# Sensor_Acquisition_Board_Rev5.net
KiCad netlist of a schematic drawn in EAGLE
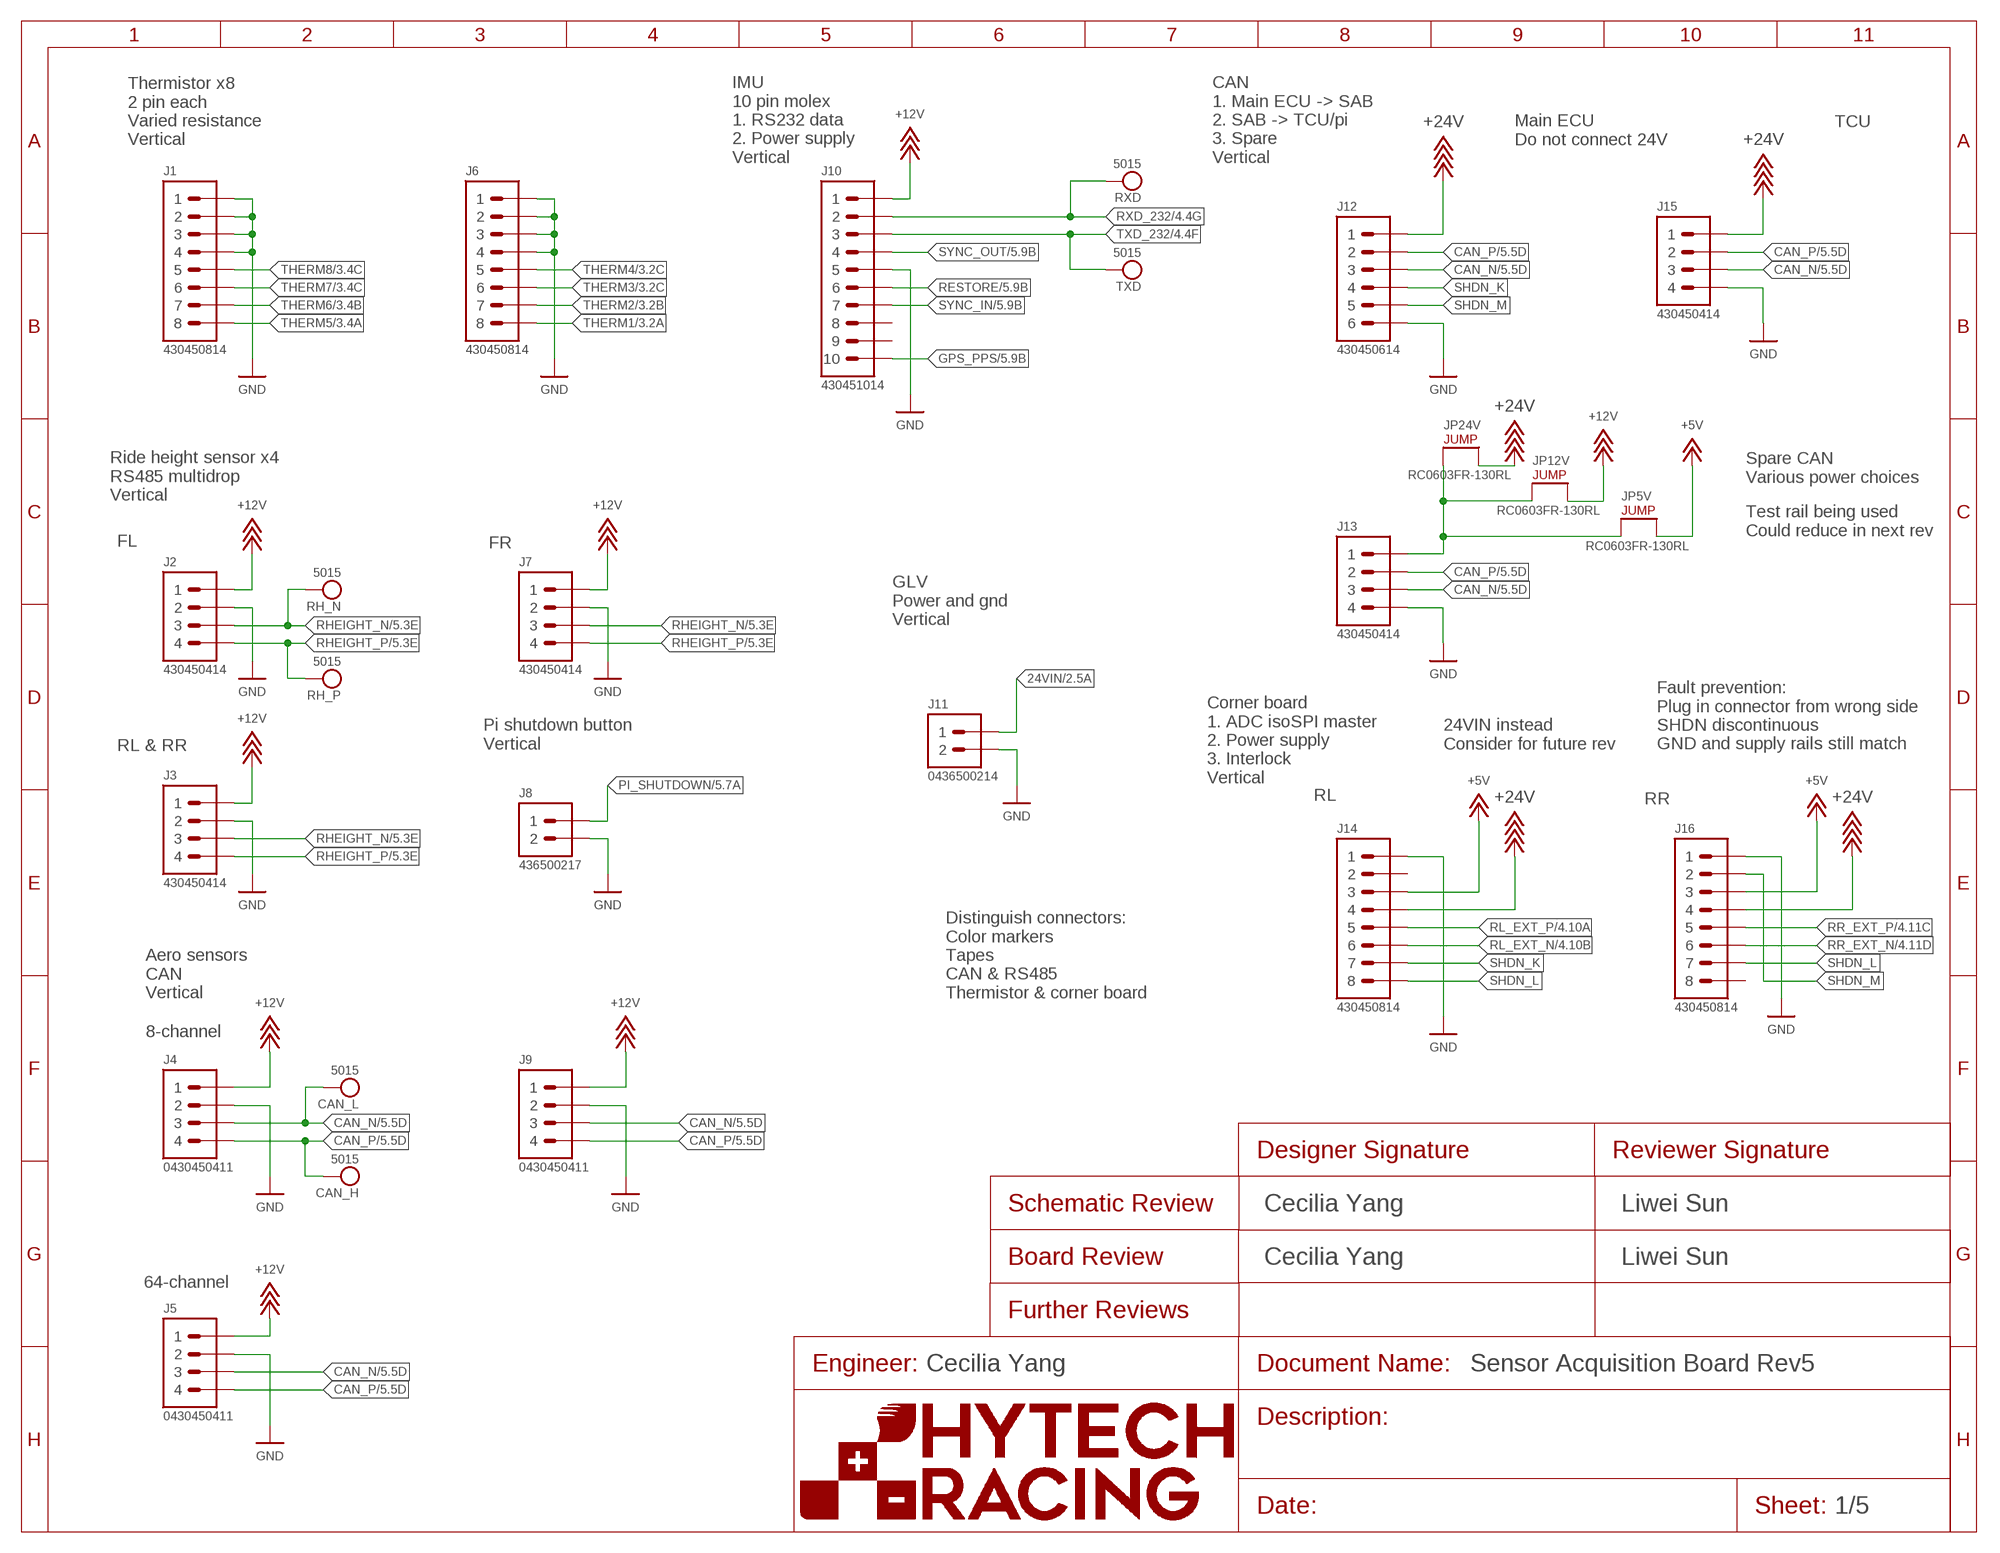
[diagram p0: schematic, sheet 1]
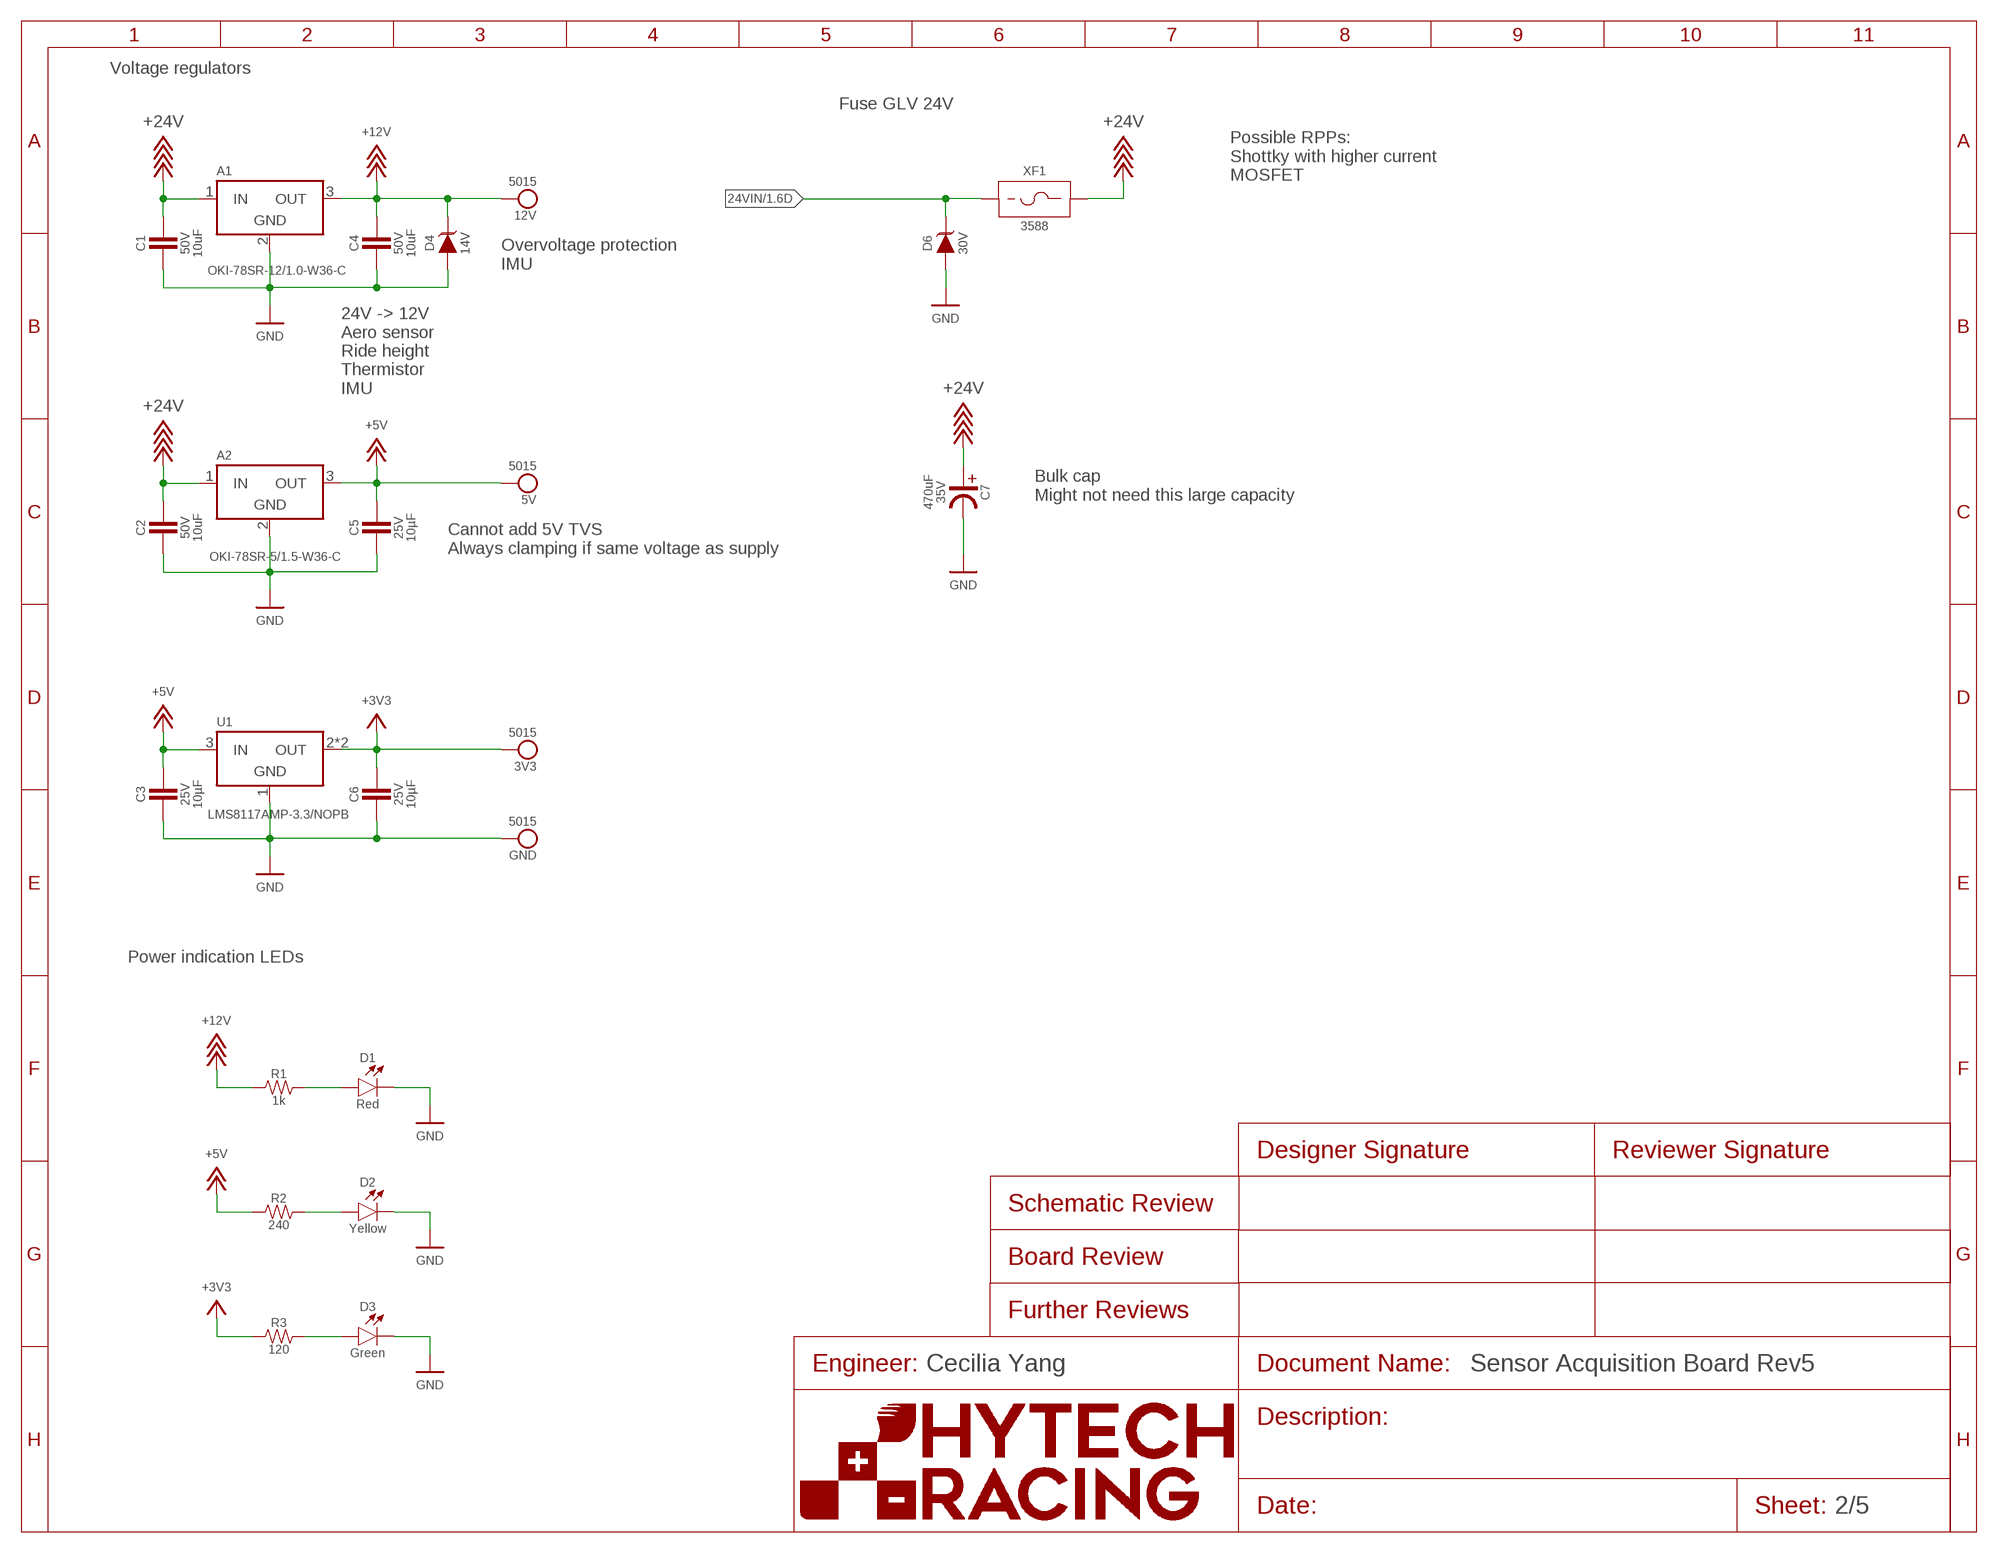
[diagram p1: schematic, sheet 2]
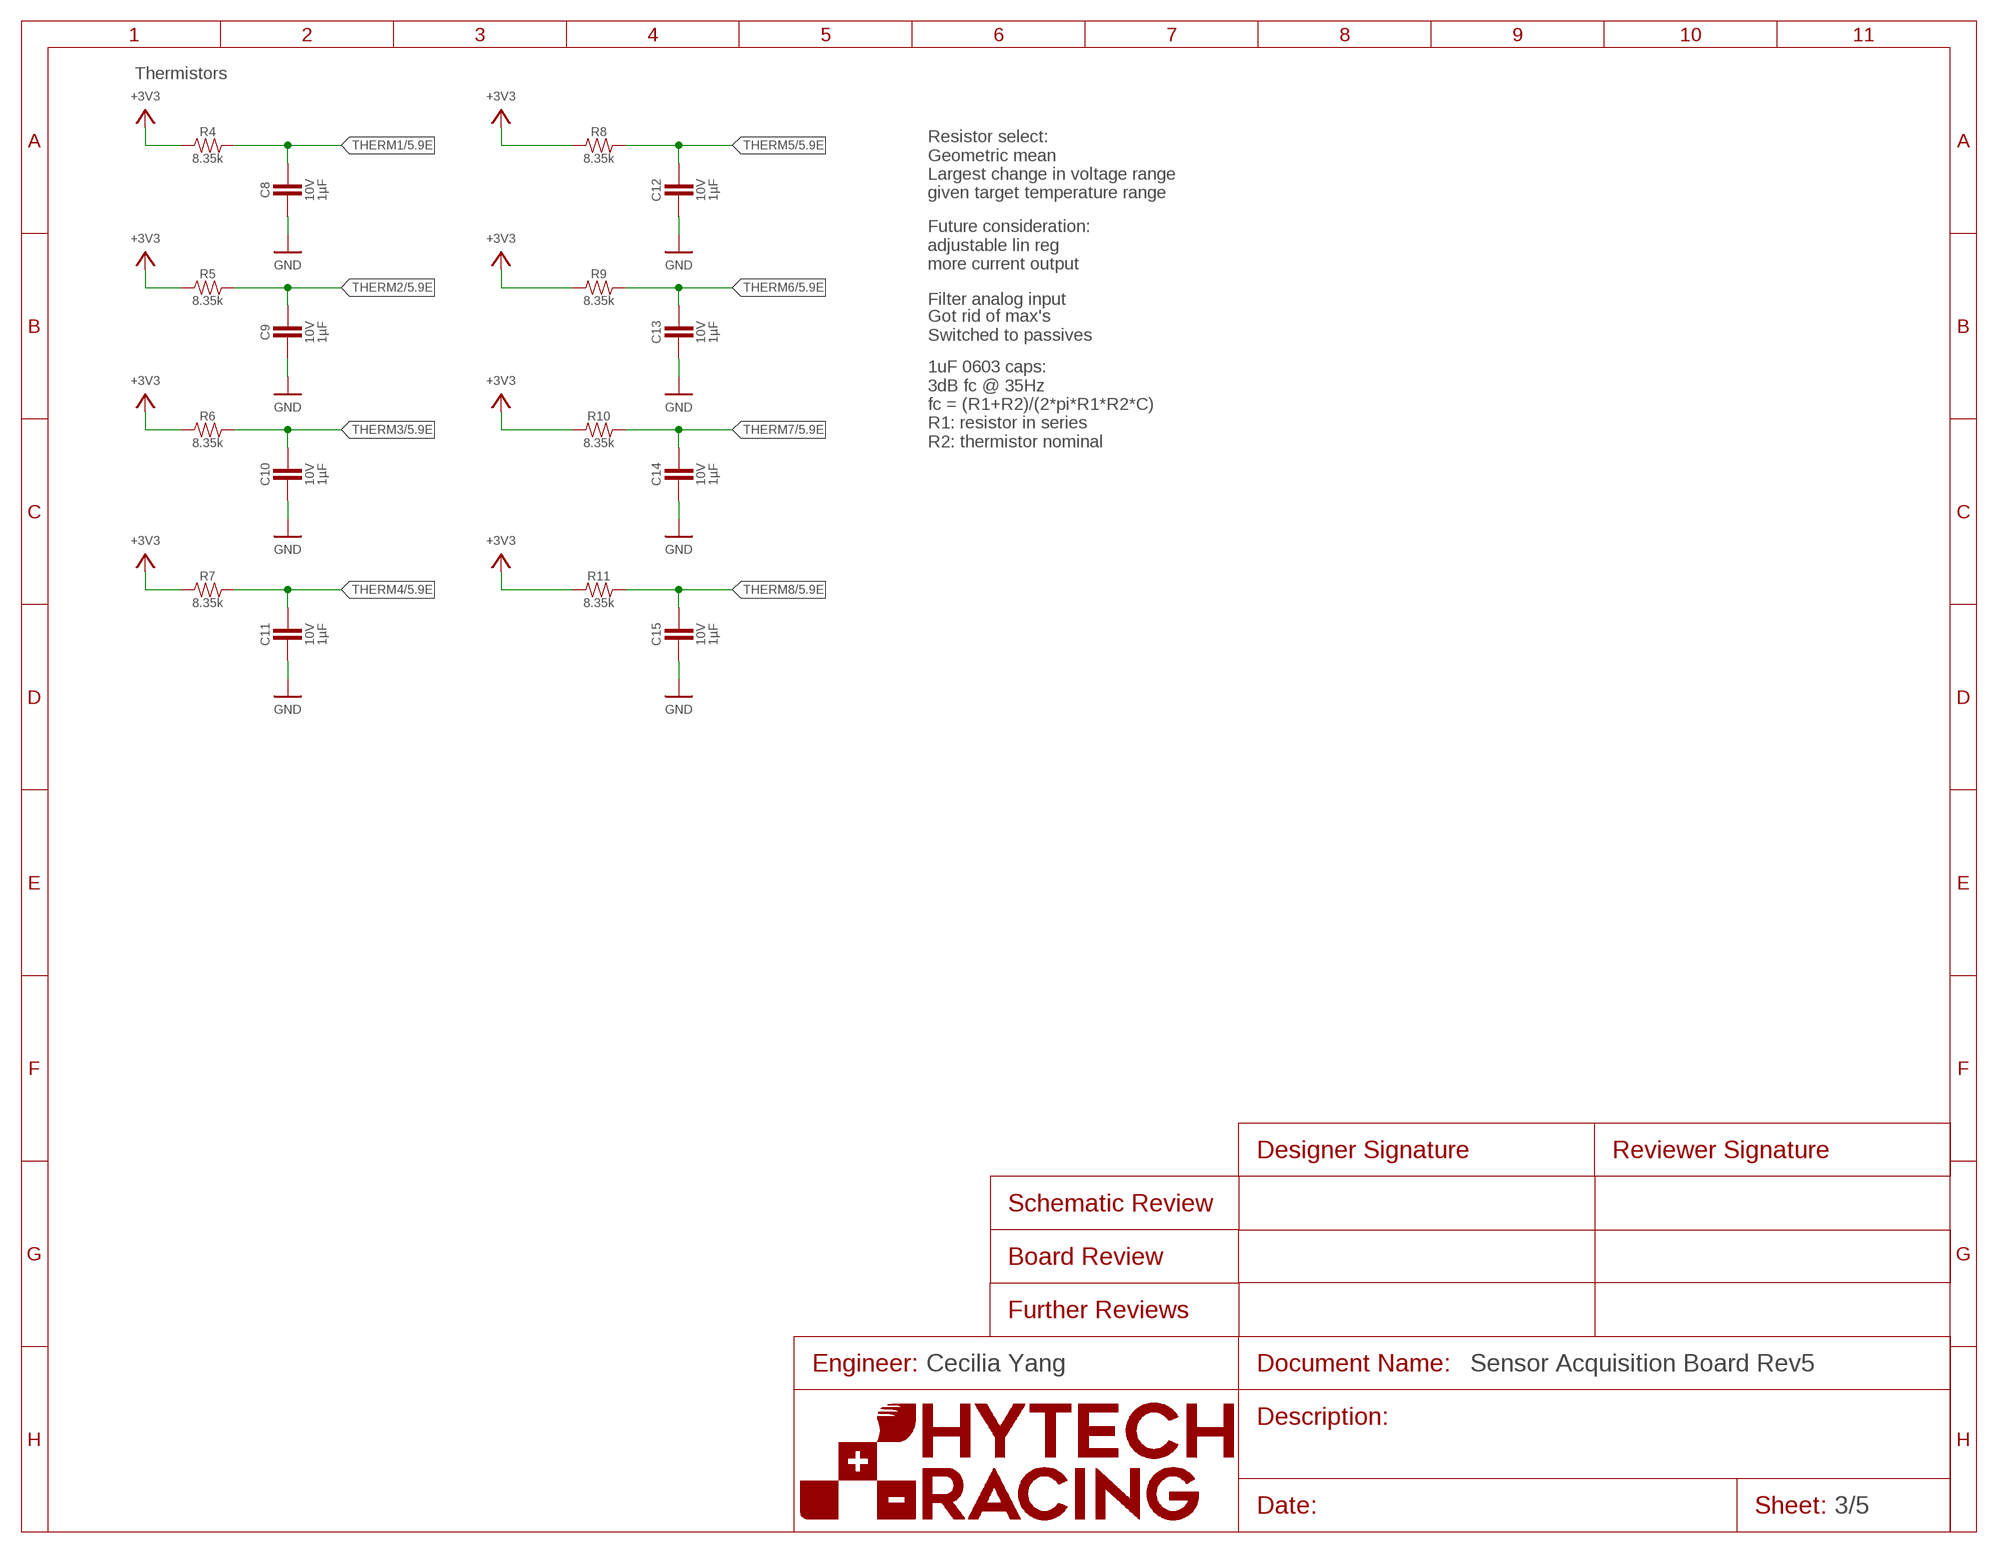
[diagram p2: schematic, sheet 3]
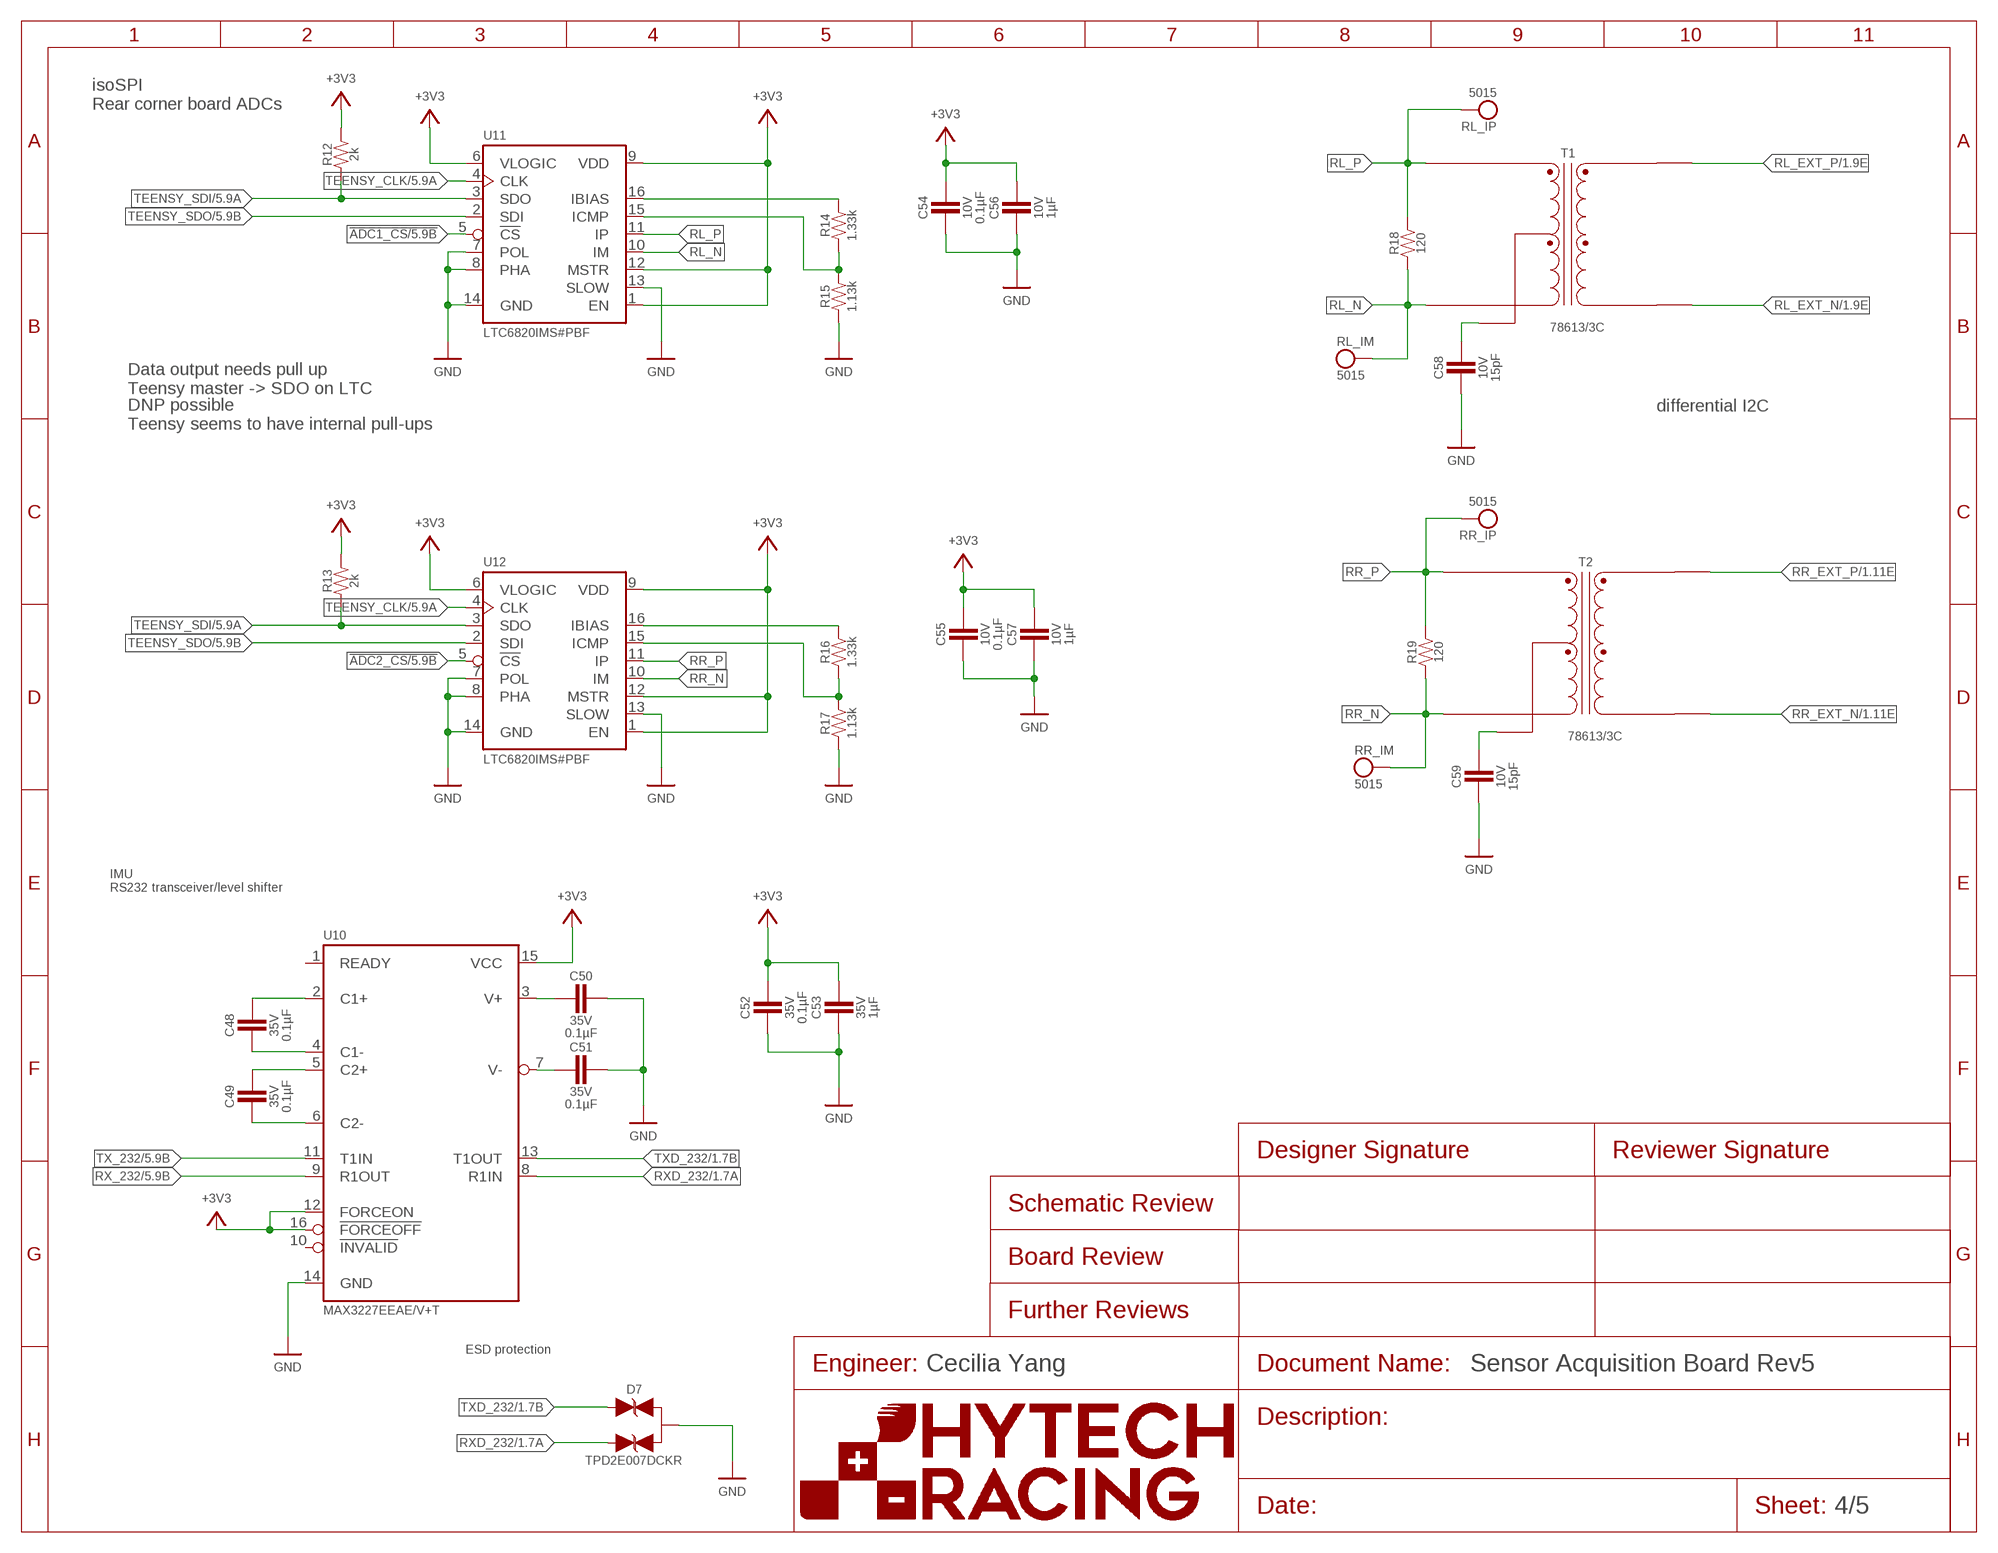
[diagram p3: schematic, sheet 4]
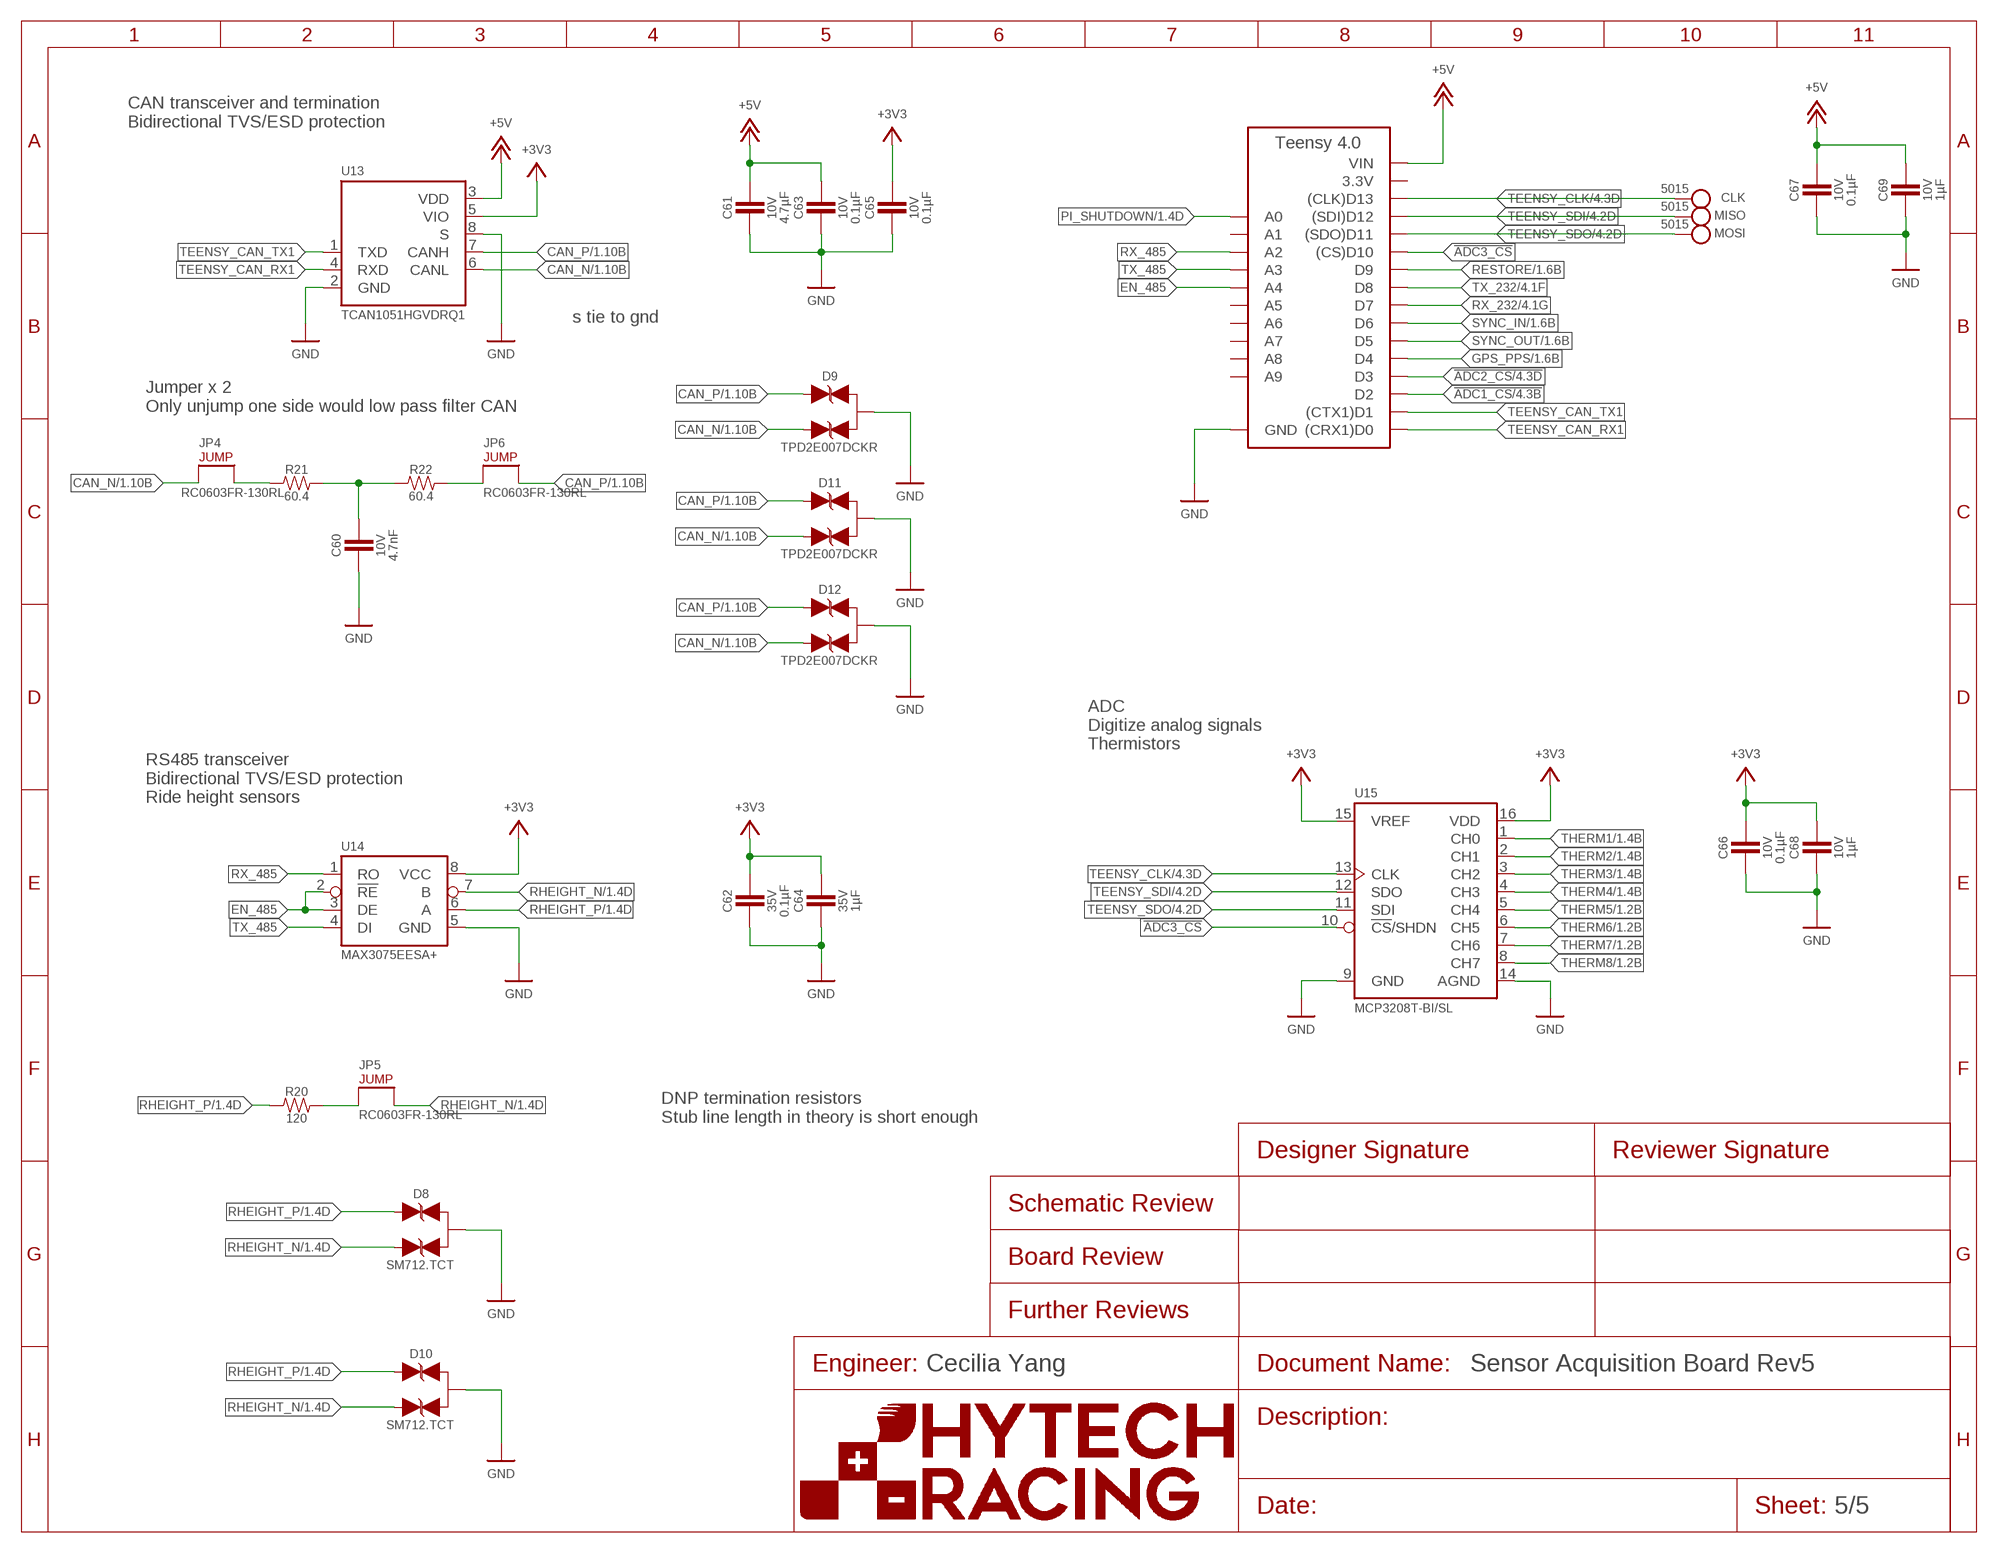
[diagram p4: schematic, sheet 5]

(export (version "E")
  (design (tool "Eeschema 10.0.6"))
  (components
    (comp (ref "CAN_H")
      (value "TEST_POINT")
      (footprint "eagle-import:5015")
      (fields (field (name "MPN") "5015") (field (name "MANUFACTURER") "Keystone Electronics"))
      (libsource (lib "eagle-import") (part "TEST_POINT"))
    )
    (comp (ref "CAN_L")
      (value "TEST_POINT")
      (footprint "eagle-import:5015")
      (fields (field (name "MPN") "5015") (field (name "MANUFACTURER") "Keystone Electronics"))
      (libsource (lib "eagle-import") (part "TEST_POINT"))
    )
    (comp (ref "J1")
      (value "CONNECTOR-8_μF_T_V_BLACK")
      (footprint "eagle-import:MOLEX_MICROFIT_PTH_VERTICAL_08_DUAL")
      (fields (field (name "MANUFACTURER") "Molex") (field (name "MPN") "430450814"))
      (libsource (lib "eagle-import") (part "CONNECTOR-8_?_μF_T_VBLACK"))
    )
    (comp (ref "J2")
      (value "CONNECTOR-4_μF_T_V_BLACK")
      (footprint "eagle-import:MOLEX_MICROFIT_PTH_VERTICAL_04_DUAL")
      (fields (field (name "MANUFACTURER") "Molex") (field (name "MPN") "430450414"))
      (libsource (lib "eagle-import") (part "CONNECTOR-4_?_μF_T_VBLACK"))
    )
    (comp (ref "J3")
      (value "CONNECTOR-4_μF_T_V_BLACK")
      (footprint "eagle-import:MOLEX_MICROFIT_PTH_VERTICAL_04_DUAL")
      (fields (field (name "MANUFACTURER") "Molex") (field (name "MPN") "430450414"))
      (libsource (lib "eagle-import") (part "CONNECTOR-4_?_μF_T_VBLACK"))
    )
    (comp (ref "J4")
      (value "CONNECTOR-4_μF_S_RA_")
      (footprint "eagle-import:MOLEX_MICROFIT_SMD_RIGHTANGLE_04_DUAL")
      (fields (field (name "MPN") "0430450411") (field (name "MANUFACTURER") "Molex"))
      (libsource (lib "eagle-import") (part "CONNECTOR-4_?_μF_S_RA"))
    )
    (comp (ref "J5")
      (value "CONNECTOR-4_μF_S_RA_")
      (footprint "eagle-import:MOLEX_MICROFIT_SMD_RIGHTANGLE_04_DUAL")
      (fields (field (name "MPN") "0430450411") (field (name "MANUFACTURER") "Molex"))
      (libsource (lib "eagle-import") (part "CONNECTOR-4_?_μF_S_RA"))
    )
    (comp (ref "J6")
      (value "CONNECTOR-8_μF_T_V_BLACK")
      (footprint "eagle-import:MOLEX_MICROFIT_PTH_VERTICAL_08_DUAL")
      (fields (field (name "MANUFACTURER") "Molex") (field (name "MPN") "430450814"))
      (libsource (lib "eagle-import") (part "CONNECTOR-8_?_μF_T_VBLACK"))
    )
    (comp (ref "J7")
      (value "CONNECTOR-4_μF_T_V_BLACK")
      (footprint "eagle-import:MOLEX_MICROFIT_PTH_VERTICAL_04_DUAL")
      (fields (field (name "MANUFACTURER") "Molex") (field (name "MPN") "430450414"))
      (libsource (lib "eagle-import") (part "CONNECTOR-4_?_μF_T_VBLACK"))
    )
    (comp (ref "J8")
      (value "CONNECTOR-2_μF_T_V_BLACK")
      (footprint "eagle-import:MOLEX_MICROFIT_PTH_VERTICAL_02_DUAL")
      (fields (field (name "MANUFACTURER") "Molex") (field (name "MPN") "436500217"))
      (libsource (lib "eagle-import") (part "CONNECTOR-2_?_μF_T_VBLACK"))
    )
    (comp (ref "J9")
      (value "CONNECTOR-4_μF_S_RA_")
      (footprint "eagle-import:MOLEX_MICROFIT_SMD_RIGHTANGLE_04_DUAL")
      (fields (field (name "MPN") "0430450411") (field (name "MANUFACTURER") "Molex"))
      (libsource (lib "eagle-import") (part "CONNECTOR-4_?_μF_S_RA"))
    )
    (comp (ref "J10")
      (value "CONNECTOR-10_MF_T_V_")
      (footprint "eagle-import:MOLEX_MICROFIT_PTH_VERTICAL_10_DUAL")
      (fields (field (name "MPN") "430451014") (field (name "MANUFACTURER") "MOLEX"))
      (libsource (lib "eagle-import") (part "CONNECTOR-10_?_MF_T_V"))
    )
    (comp (ref "J11")
      (value "CONNECTOR-2_MICROFIT_SMD_RIGHTANGLE_02_SINGLE_BLACK")
      (footprint "eagle-import:MOLEX_MICROFIT_SMD_RIGHTANGLE_02_SINGLE")
      (fields (field (name "MANUFACTURER") "Molex") (field (name "MPN") "0436500214"))
      (libsource (lib "eagle-import") (part "CONNECTOR-2_?_MICROFIT_SMD_RIGHTANGLE_02_SINGLEBLACK"))
    )
    (comp (ref "J12")
      (value "CONNECTOR-6_μF_T_V_BLACK")
      (footprint "eagle-import:MOLEX_MICROFIT_PTH_VERTICAL_06_DUAL")
      (fields (field (name "MANUFACTURER") "Molex") (field (name "MPN") "430450614"))
      (libsource (lib "eagle-import") (part "CONNECTOR-6_?_μF_T_VBLACK"))
    )
    (comp (ref "J13")
      (value "CONNECTOR-4_μF_T_V_BLACK")
      (footprint "eagle-import:MOLEX_MICROFIT_PTH_VERTICAL_04_DUAL")
      (fields (field (name "MANUFACTURER") "Molex") (field (name "MPN") "430450414"))
      (libsource (lib "eagle-import") (part "CONNECTOR-4_?_μF_T_VBLACK"))
    )
    (comp (ref "J14")
      (value "CONNECTOR-8_μF_T_V_BLACK")
      (footprint "eagle-import:MOLEX_MICROFIT_PTH_VERTICAL_08_DUAL")
      (fields (field (name "MANUFACTURER") "Molex") (field (name "MPN") "430450814"))
      (libsource (lib "eagle-import") (part "CONNECTOR-8_?_μF_T_VBLACK"))
    )
    (comp (ref "J15")
      (value "CONNECTOR-4_μF_T_V_BLACK")
      (footprint "eagle-import:MOLEX_MICROFIT_PTH_VERTICAL_04_DUAL")
      (fields (field (name "MANUFACTURER") "Molex") (field (name "MPN") "430450414"))
      (libsource (lib "eagle-import") (part "CONNECTOR-4_?_μF_T_VBLACK"))
    )
    (comp (ref "J16")
      (value "CONNECTOR-8_μF_T_V_BLACK")
      (footprint "eagle-import:MOLEX_MICROFIT_PTH_VERTICAL_08_DUAL")
      (fields (field (name "MANUFACTURER") "Molex") (field (name "MPN") "430450814"))
      (libsource (lib "eagle-import") (part "CONNECTOR-8_?_μF_T_VBLACK"))
    )
    (comp (ref "JP5V")
      (value "JUMPER_0603_")
      (footprint "eagle-import:0603-RES")
      (fields (field (name "MPN") "RC0603FR-130RL") (field (name "MANUFACTURER") "YAGEO"))
      (libsource (lib "eagle-import") (part "JUMPER_?_0603"))
    )
    (comp (ref "JP12V")
      (value "JUMPER_0603_")
      (footprint "eagle-import:0603-RES")
      (fields (field (name "MPN") "RC0603FR-130RL") (field (name "MANUFACTURER") "YAGEO"))
      (libsource (lib "eagle-import") (part "JUMPER_?_0603"))
    )
    (comp (ref "JP24V")
      (value "JUMPER_0603_")
      (footprint "eagle-import:0603-RES")
      (fields (field (name "MPN") "RC0603FR-130RL") (field (name "MANUFACTURER") "YAGEO"))
      (libsource (lib "eagle-import") (part "JUMPER_?_0603"))
    )
    (comp (ref "RH_N")
      (value "TEST_POINT")
      (footprint "eagle-import:5015")
      (fields (field (name "MPN") "5015") (field (name "MANUFACTURER") "Keystone Electronics"))
      (libsource (lib "eagle-import") (part "TEST_POINT"))
    )
    (comp (ref "RH_P")
      (value "TEST_POINT")
      (footprint "eagle-import:5015")
      (fields (field (name "MPN") "5015") (field (name "MANUFACTURER") "Keystone Electronics"))
      (libsource (lib "eagle-import") (part "TEST_POINT"))
    )
    (comp (ref "RXD")
      (value "TEST_POINT")
      (footprint "eagle-import:5015")
      (fields (field (name "MPN") "5015") (field (name "MANUFACTURER") "Keystone Electronics"))
      (libsource (lib "eagle-import") (part "TEST_POINT"))
    )
    (comp (ref "TXD")
      (value "TEST_POINT")
      (footprint "eagle-import:5015")
      (fields (field (name "MPN") "5015") (field (name "MANUFACTURER") "Keystone Electronics"))
      (libsource (lib "eagle-import") (part "TEST_POINT"))
    )
    (comp (ref "C48")
      (value "CAPACITOR_0603_35V_0.1UF")
      (footprint "eagle-import:0603-CAP")
      (fields
        (field (name "CAPACITANCE") "0.1µF")
        (field (name "MANUFACTURER") "Taiyo Yuden")
        (field (name "MPN") "GMK107B7104KAHT")
        (field (name "TOLERANCE") "10%")
        (field (name "VOLTAGE") "35V")
      )
      (libsource (lib "eagle-import") (part "CAPACITOR_?_060335V_0.1UF"))
    )
    (comp (ref "C49")
      (value "CAPACITOR_0603_35V_0.1UF")
      (footprint "eagle-import:0603-CAP")
      (fields
        (field (name "CAPACITANCE") "0.1µF")
        (field (name "MANUFACTURER") "Taiyo Yuden")
        (field (name "MPN") "GMK107B7104KAHT")
        (field (name "TOLERANCE") "10%")
        (field (name "VOLTAGE") "35V")
      )
      (libsource (lib "eagle-import") (part "CAPACITOR_?_060335V_0.1UF"))
    )
    (comp (ref "C50")
      (value "CAPACITOR_0603_35V_0.1UF")
      (footprint "eagle-import:0603-CAP")
      (fields
        (field (name "CAPACITANCE") "0.1µF")
        (field (name "MANUFACTURER") "Taiyo Yuden")
        (field (name "MPN") "GMK107B7104KAHT")
        (field (name "TOLERANCE") "10%")
        (field (name "VOLTAGE") "35V")
      )
      (libsource (lib "eagle-import") (part "CAPACITOR_?_060335V_0.1UF"))
    )
    (comp (ref "C51")
      (value "CAPACITOR_0603_35V_0.1UF")
      (footprint "eagle-import:0603-CAP")
      (fields
        (field (name "CAPACITANCE") "0.1µF")
        (field (name "MANUFACTURER") "Taiyo Yuden")
        (field (name "MPN") "GMK107B7104KAHT")
        (field (name "TOLERANCE") "10%")
        (field (name "VOLTAGE") "35V")
      )
      (libsource (lib "eagle-import") (part "CAPACITOR_?_060335V_0.1UF"))
    )
    (comp (ref "C52")
      (value "CAPACITOR_0603_35V_0.1UF")
      (footprint "eagle-import:0603-CAP")
      (fields
        (field (name "CAPACITANCE") "0.1µF")
        (field (name "MANUFACTURER") "Taiyo Yuden")
        (field (name "MPN") "GMK107B7104KAHT")
        (field (name "TOLERANCE") "10%")
        (field (name "VOLTAGE") "35V")
      )
      (libsource (lib "eagle-import") (part "CAPACITOR_?_060335V_0.1UF"))
    )
    (comp (ref "C53")
      (value "CAPACITOR_0603_35V_1UF")
      (footprint "eagle-import:0603-CAP")
      (fields
        (field (name "CAPACITANCE") "1µF")
        (field (name "MANUFACTURER") "TDK Corporation")
        (field (name "MPN") "C1608X7R1V105K080AE")
        (field (name "TOLERANCE") "10%")
        (field (name "VOLTAGE") "35V")
      )
      (libsource (lib "eagle-import") (part "CAPACITOR_?_060335V_1UF"))
    )
    (comp (ref "C54")
      (value "CAPACITOR_0603_10V_0.1UF")
      (footprint "eagle-import:0603-CAP")
      (fields
        (field (name "CAPACITANCE") "0.1µF")
        (field (name "MANUFACTURER") "Vishay Vitramon")
        (field (name "MPN") "VJ0603Y104JXQPW1BC")
        (field (name "TOLERANCE") "5%")
        (field (name "VOLTAGE") "10V")
      )
      (libsource (lib "eagle-import") (part "CAPACITOR_?_060310V_0.1UF"))
    )
    (comp (ref "C55")
      (value "CAPACITOR_0603_10V_0.1UF")
      (footprint "eagle-import:0603-CAP")
      (fields
        (field (name "CAPACITANCE") "0.1µF")
        (field (name "MANUFACTURER") "Vishay Vitramon")
        (field (name "MPN") "VJ0603Y104JXQPW1BC")
        (field (name "TOLERANCE") "5%")
        (field (name "VOLTAGE") "10V")
      )
      (libsource (lib "eagle-import") (part "CAPACITOR_?_060310V_0.1UF"))
    )
    (comp (ref "C56")
      (value "CAPACITOR_0603_10V_1UF")
      (footprint "eagle-import:0603-CAP")
      (fields
        (field (name "CAPACITANCE") "1µF")
        (field (name "MANUFACTURER") "Yageo")
        (field (name "MPN") "CC0603KRX7R6BB105")
        (field (name "TOLERANCE") "10%")
        (field (name "VOLTAGE") "10V")
      )
      (libsource (lib "eagle-import") (part "CAPACITOR_?_060310V_1UF"))
    )
    (comp (ref "C57")
      (value "CAPACITOR_0603_10V_1UF")
      (footprint "eagle-import:0603-CAP")
      (fields
        (field (name "CAPACITANCE") "1µF")
        (field (name "MANUFACTURER") "Yageo")
        (field (name "MPN") "CC0603KRX7R6BB105")
        (field (name "TOLERANCE") "10%")
        (field (name "VOLTAGE") "10V")
      )
      (libsource (lib "eagle-import") (part "CAPACITOR_?_060310V_1UF"))
    )
    (comp (ref "C58")
      (value "CAPACITOR_0603_10V_15PF")
      (footprint "eagle-import:0603-CAP")
      (fields
        (field (name "CAPACITANCE") "15pF")
        (field (name "MANUFACTURER") "Vishay Vitramon")
        (field (name "MPN") "VJ0603A150FXQPW1BC")
        (field (name "TOLERANCE") "1%")
        (field (name "VOLTAGE") "10V")
      )
      (libsource (lib "eagle-import") (part "CAPACITOR_?_060310V_15PF"))
    )
    (comp (ref "C59")
      (value "CAPACITOR_0603_10V_15PF")
      (footprint "eagle-import:0603-CAP")
      (fields
        (field (name "CAPACITANCE") "15pF")
        (field (name "MANUFACTURER") "Vishay Vitramon")
        (field (name "MPN") "VJ0603A150FXQPW1BC")
        (field (name "TOLERANCE") "1%")
        (field (name "VOLTAGE") "10V")
      )
      (libsource (lib "eagle-import") (part "CAPACITOR_?_060310V_15PF"))
    )
    (comp (ref "D7")
      (value "TVS_BIDIRECTIONAL_DUAL")
      (footprint "eagle-import:SC-70-3")
      (fields (field (name "MPN") "TPD2E007DCKR") (field (name "MANUFACTURER") "Texas Instruments"))
      (libsource (lib "eagle-import") (part "TVS_BIDIRECTIONAL_DUAL"))
    )
    (comp (ref "R12")
      (value "RESISTOR_0603_2K")
      (footprint "eagle-import:0603-RES")
      (fields
        (field (name "MANUFACTURER") "Panasonic Electronic Components")
        (field (name "MPN") "ERJ-UP3F2001V")
        (field (name "POWER") "0.25W")
        (field (name "RESISTANCE") "2k")
      )
      (libsource (lib "eagle-import") (part "RESISTOR_?_06032K"))
    )
    (comp (ref "R13")
      (value "RESISTOR_0603_2K")
      (footprint "eagle-import:0603-RES")
      (fields
        (field (name "MANUFACTURER") "Panasonic Electronic Components")
        (field (name "MPN") "ERJ-UP3F2001V")
        (field (name "POWER") "0.25W")
        (field (name "RESISTANCE") "2k")
      )
      (libsource (lib "eagle-import") (part "RESISTOR_?_06032K"))
    )
    (comp (ref "R14")
      (value "RESISTOR_0603_1.33K")
      (footprint "eagle-import:0603-RES")
      (fields
        (field (name "MANUFACTURER") "Panasonic Electronic Components")
        (field (name "MPN") "ERA-3AEB1331V")
        (field (name "POWER") "0.1W")
        (field (name "RESISTANCE") "1.33k")
      )
      (libsource (lib "eagle-import") (part "RESISTOR_?_06031.33K"))
    )
    (comp (ref "R15")
      (value "RESISTOR_0603_1.13K")
      (footprint "eagle-import:0603-RES")
      (fields
        (field (name "MANUFACTURER") "Panasonic Electronic Components")
        (field (name "MPN") "ERJ-3EKF1131V")
        (field (name "POWER") "0.1W")
        (field (name "RESISTANCE") "1.13k")
      )
      (libsource (lib "eagle-import") (part "RESISTOR_?_06031.13K"))
    )
    (comp (ref "R16")
      (value "RESISTOR_0603_1.33K")
      (footprint "eagle-import:0603-RES")
      (fields
        (field (name "MANUFACTURER") "Panasonic Electronic Components")
        (field (name "MPN") "ERA-3AEB1331V")
        (field (name "POWER") "0.1W")
        (field (name "RESISTANCE") "1.33k")
      )
      (libsource (lib "eagle-import") (part "RESISTOR_?_06031.33K"))
    )
    (comp (ref "R17")
      (value "RESISTOR_0603_1.13K")
      (footprint "eagle-import:0603-RES")
      (fields
        (field (name "MANUFACTURER") "Panasonic Electronic Components")
        (field (name "MPN") "ERJ-3EKF1131V")
        (field (name "POWER") "0.1W")
        (field (name "RESISTANCE") "1.13k")
      )
      (libsource (lib "eagle-import") (part "RESISTOR_?_06031.13K"))
    )
    (comp (ref "R18")
      (value "RESISTOR_0603_120")
      (footprint "eagle-import:0603-RES")
      (fields
        (field (name "MANUFACTURER") "Panasonic Electronic Components")
        (field (name "MPN") "ERA-3AEB121V")
        (field (name "POWER") "0.1W")
        (field (name "RESISTANCE") "120")
      )
      (libsource (lib "eagle-import") (part "RESISTOR_?_0603120"))
    )
    (comp (ref "R19")
      (value "RESISTOR_0603_120")
      (footprint "eagle-import:0603-RES")
      (fields
        (field (name "MANUFACTURER") "Panasonic Electronic Components")
        (field (name "MPN") "ERA-3AEB121V")
        (field (name "POWER") "0.1W")
        (field (name "RESISTANCE") "120")
      )
      (libsource (lib "eagle-import") (part "RESISTOR_?_0603120"))
    )
    (comp (ref "RL_IM")
      (value "TEST_POINT")
      (footprint "eagle-import:5015")
      (fields (field (name "MPN") "5015") (field (name "MANUFACTURER") "Keystone Electronics"))
      (libsource (lib "eagle-import") (part "TEST_POINT"))
    )
    (comp (ref "RL_IP")
      (value "TEST_POINT")
      (footprint "eagle-import:5015")
      (fields (field (name "MPN") "5015") (field (name "MANUFACTURER") "Keystone Electronics"))
      (libsource (lib "eagle-import") (part "TEST_POINT"))
    )
    (comp (ref "RR_IM")
      (value "TEST_POINT")
      (footprint "eagle-import:5015")
      (fields (field (name "MPN") "5015") (field (name "MANUFACTURER") "Keystone Electronics"))
      (libsource (lib "eagle-import") (part "TEST_POINT"))
    )
    (comp (ref "RR_IP")
      (value "TEST_POINT")
      (footprint "eagle-import:5015")
      (fields (field (name "MPN") "5015") (field (name "MANUFACTURER") "Keystone Electronics"))
      (libsource (lib "eagle-import") (part "TEST_POINT"))
    )
    (comp (ref "T1")
      (value "78613/3C_78613/3C")
      (footprint "eagle-import:78613_3C")
      (fields (field (name "MPN") "78613/3C") (field (name "MANUFACTURER") "Murata Power Solutions"))
      (libsource (lib "eagle-import") (part "78613/3C_78613/3C"))
    )
    (comp (ref "T2")
      (value "78613/3C_78613/3C")
      (footprint "eagle-import:78613_3C")
      (fields (field (name "MPN") "78613/3C") (field (name "MANUFACTURER") "Murata Power Solutions"))
      (libsource (lib "eagle-import") (part "78613/3C_78613/3C"))
    )
    (comp (ref "U10")
      (value "MAX3227")
      (footprint "eagle-import:SSOP-16")
      (fields (field (name "MPN") "MAX3227EEAE/V+T") (field (name "MANUFACTURER") "Analog Devices Inc."))
      (libsource (lib "eagle-import") (part "MAX3227"))
    )
    (comp (ref "U11")
      (value "LTC6820")
      (footprint "eagle-import:MSOP-16")
      (fields (field (name "MPN") "LTC6820IMS#PBF") (field (name "MANUFACTURER") "Analog Devices"))
      (libsource (lib "eagle-import") (part "LTC6820"))
    )
    (comp (ref "U12")
      (value "LTC6820")
      (footprint "eagle-import:MSOP-16")
      (fields (field (name "MPN") "LTC6820IMS#PBF") (field (name "MANUFACTURER") "Analog Devices"))
      (libsource (lib "eagle-import") (part "LTC6820"))
    )
    (comp (ref "3V3")
      (value "TEST_POINT")
      (footprint "eagle-import:5015")
      (fields (field (name "MPN") "5015") (field (name "MANUFACTURER") "Keystone Electronics"))
      (libsource (lib "eagle-import") (part "TEST_POINT"))
    )
    (comp (ref "5V")
      (value "TEST_POINT")
      (footprint "eagle-import:5015")
      (fields (field (name "MPN") "5015") (field (name "MANUFACTURER") "Keystone Electronics"))
      (libsource (lib "eagle-import") (part "TEST_POINT"))
    )
    (comp (ref "12V")
      (value "TEST_POINT")
      (footprint "eagle-import:5015")
      (fields (field (name "MPN") "5015") (field (name "MANUFACTURER") "Keystone Electronics"))
      (libsource (lib "eagle-import") (part "TEST_POINT"))
    )
    (comp (ref "A1")
      (value "VOLTAGE_REGULATOR_MODULE_OKI-78SR_12V")
      (footprint "eagle-import:OKI-78SR")
      (fields
        (field (name "MANUFACTURER") "Murata Power Solutions Inc.")
        (field (name "MPN") "OKI-78SR-12/1.0-W36-C")
      )
      (libsource (lib "eagle-import") (part "VOLTAGE_REGULATOR_MODULE_?_OKI-78SR12V"))
    )
    (comp (ref "A2")
      (value "VOLTAGE_REGULATOR_MODULE_OKI-78SR_5V")
      (footprint "eagle-import:OKI-78SR")
      (fields
        (field (name "MANUFACTURER") "Murata Power Solutions Inc.")
        (field (name "MPN") "OKI-78SR-5/1.5-W36-C")
      )
      (libsource (lib "eagle-import") (part "VOLTAGE_REGULATOR_MODULE_?_OKI-78SR5V"))
    )
    (comp (ref "C1")
      (value "CAPACITOR_0805_50V_10UF")
      (footprint "eagle-import:0805-CAP")
      (fields
        (field (name "CAPACITANCE") "10uF")
        (field (name "MANUFACTURER") "Murata")
        (field (name "MPN") " GRM21BR61H106KE43L")
        (field (name "TOLERANCE") "10%")
        (field (name "VOLTAGE") "50V")
      )
      (libsource (lib "eagle-import") (part "CAPACITOR_?_080550V_10UF"))
    )
    (comp (ref "C2")
      (value "CAPACITOR_0805_50V_10UF")
      (footprint "eagle-import:0805-CAP")
      (fields
        (field (name "CAPACITANCE") "10uF")
        (field (name "MANUFACTURER") "Murata")
        (field (name "MPN") " GRM21BR61H106KE43L")
        (field (name "TOLERANCE") "10%")
        (field (name "VOLTAGE") "50V")
      )
      (libsource (lib "eagle-import") (part "CAPACITOR_?_080550V_10UF"))
    )
    (comp (ref "C3")
      (value "CAPACITOR_0603_25V_10UF")
      (footprint "eagle-import:0603-CAP")
      (fields
        (field (name "CAPACITANCE") "10µF")
        (field (name "MANUFACTURER") "Murata Electronics")
        (field (name "MPN") "GRM188R61E106MA73D")
        (field (name "TOLERANCE") "20%")
        (field (name "VOLTAGE") "25V")
      )
      (libsource (lib "eagle-import") (part "CAPACITOR_?_060325V_10UF"))
    )
    (comp (ref "C4")
      (value "CAPACITOR_0805_50V_10UF")
      (footprint "eagle-import:0805-CAP")
      (fields
        (field (name "CAPACITANCE") "10uF")
        (field (name "MANUFACTURER") "Murata")
        (field (name "MPN") " GRM21BR61H106KE43L")
        (field (name "TOLERANCE") "10%")
        (field (name "VOLTAGE") "50V")
      )
      (libsource (lib "eagle-import") (part "CAPACITOR_?_080550V_10UF"))
    )
    (comp (ref "C5")
      (value "CAPACITOR_0603_25V_10UF")
      (footprint "eagle-import:0603-CAP")
      (fields
        (field (name "CAPACITANCE") "10µF")
        (field (name "MANUFACTURER") "Murata Electronics")
        (field (name "MPN") "GRM188R61E106MA73D")
        (field (name "TOLERANCE") "20%")
        (field (name "VOLTAGE") "25V")
      )
      (libsource (lib "eagle-import") (part "CAPACITOR_?_060325V_10UF"))
    )
    (comp (ref "C6")
      (value "CAPACITOR_0603_25V_10UF")
      (footprint "eagle-import:0603-CAP")
      (fields
        (field (name "CAPACITANCE") "10µF")
        (field (name "MANUFACTURER") "Murata Electronics")
        (field (name "MPN") "GRM188R61E106MA73D")
        (field (name "TOLERANCE") "20%")
        (field (name "VOLTAGE") "25V")
      )
      (libsource (lib "eagle-import") (part "CAPACITOR_?_060325V_10UF"))
    )
    (comp (ref "C7")
      (value "CAPACITOR_ELECTROLYTIC_EEH_AZS_470UF")
      (footprint "eagle-import:EEH-AZS")
      (fields
        (field (name "CAPACITANCE") "470uF")
        (field (name "MANUFACTURER") "Panasonic Electronic Components")
        (field (name "MPN") "EEH-AZS1V471B")
        (field (name "TOLERANCE") "20&")
        (field (name "VOLTAGE") "35V")
      )
      (libsource (lib "eagle-import") (part "CAPACITOR_ELECTROLYTIC_?_EEH_AZS470UF"))
    )
    (comp (ref "D1")
      (value "LED_0603_RED")
      (footprint "eagle-import:0603-LED")
      (fields
        (field (name "COLOR") "Red")
        (field (name "MANUFACTURER") "Kingbright")
        (field (name "MPN") "APT1608SECK/J3-PRV")
      )
      (libsource (lib "eagle-import") (part "LED_?_0603RED"))
    )
    (comp (ref "D2")
      (value "LED_0603_YELLOW")
      (footprint "eagle-import:0603-LED")
      (fields
        (field (name "COLOR") "Yellow")
        (field (name "MANUFACTURER") "Kingbright")
        (field (name "MPN") "APT1608SYCK/J3-PRV")
      )
      (libsource (lib "eagle-import") (part "LED_?_0603YELLOW"))
    )
    (comp (ref "D3")
      (value "LED_0603_GREEN")
      (footprint "eagle-import:0603-LED")
      (fields
        (field (name "COLOR") "Green")
        (field (name "MANUFACTURER") "Kingbright")
        (field (name "MPN") "APT1608ZGCK")
      )
      (libsource (lib "eagle-import") (part "LED_?_0603GREEN"))
    )
    (comp (ref "D4")
      (value "TVS_DO-219AB_14V")
      (footprint "eagle-import:SMF")
      (fields
        (field (name "MANUFACTURER") "Vishay General Semiconductor")
        (field (name "MPN") "SMF14A-E3-08")
        (field (name "VOLTAGE") "14V")
      )
      (libsource (lib "eagle-import") (part "TVS_?_DO-219AB14V"))
    )
    (comp (ref "D6")
      (value "TVS_DO-214AA_30V")
      (footprint "eagle-import:1.5SMBJ")
      (fields
        (field (name "MANUFACTURER") "Bourns Inc.")
        (field (name "MPN") " 1.5SMBJ30A")
        (field (name "VOLTAGE") "30V")
      )
      (libsource (lib "eagle-import") (part "TVS_?_DO-214AA30V"))
    )
    (comp (ref "GND")
      (value "TEST_POINT")
      (footprint "eagle-import:5015")
      (fields (field (name "MPN") "5015") (field (name "MANUFACTURER") "Keystone Electronics"))
      (libsource (lib "eagle-import") (part "TEST_POINT"))
    )
    (comp (ref "R1")
      (value "RESISTOR_0603_1K")
      (footprint "eagle-import:0603-RES")
      (fields
        (field (name "MANUFACTURER") "TE Connectivity Passive Product")
        (field (name "MPN") " CPF-A-0603B1K0E")
        (field (name "POWER") "0.0625W")
        (field (name "RESISTANCE") "1k")
      )
      (libsource (lib "eagle-import") (part "RESISTOR_?_06031K"))
    )
    (comp (ref "R2")
      (value "RESISTOR_0603_240")
      (footprint "eagle-import:0603-RES")
      (fields
        (field (name "MANUFACTURER") "Yageo")
        (field (name "MPN") "RC0603FR-07240RL")
        (field (name "POWER") "0.1W")
        (field (name "RESISTANCE") "240")
      )
      (libsource (lib "eagle-import") (part "RESISTOR_?_0603240"))
    )
    (comp (ref "R3")
      (value "RESISTOR_0603_120")
      (footprint "eagle-import:0603-RES")
      (fields
        (field (name "MANUFACTURER") "Panasonic Electronic Components")
        (field (name "MPN") "ERA-3AEB121V")
        (field (name "POWER") "0.1W")
        (field (name "RESISTANCE") "120")
      )
      (libsource (lib "eagle-import") (part "RESISTOR_?_0603120"))
    )
    (comp (ref "U1")
      (value "VOLTAGE_REGULATOR_SOT-223_3.3V")
      (footprint "eagle-import:SOT-223")
      (fields (field (name "MANUFACTURER") "Texas Instruments") (field (name "MPN") "LMS8117AMP-3.3/NOPB"))
      (libsource (lib "eagle-import") (part "VOLTAGE_REGULATOR_?_SOT-2233.3V"))
    )
    (comp (ref "XF1")
      (value "FUSE_HOLDER_MINIBLADESMD")
      (footprint "eagle-import:3588")
      (fields (field (name "MANUFACTURER") "Keystone Electronics") (field (name "MPN") "3588"))
      (libsource (lib "eagle-import") (part "FUSE_HOLDER_SMDMINIBLADE"))
    )
    (comp (ref "C8")
      (value "CAPACITOR_0603_10V_1UF")
      (footprint "eagle-import:0603-CAP")
      (fields
        (field (name "CAPACITANCE") "1µF")
        (field (name "MANUFACTURER") "Yageo")
        (field (name "MPN") "CC0603KRX7R6BB105")
        (field (name "TOLERANCE") "10%")
        (field (name "VOLTAGE") "10V")
      )
      (libsource (lib "eagle-import") (part "CAPACITOR_?_060310V_1UF"))
    )
    (comp (ref "C9")
      (value "CAPACITOR_0603_10V_1UF")
      (footprint "eagle-import:0603-CAP")
      (fields
        (field (name "CAPACITANCE") "1µF")
        (field (name "MANUFACTURER") "Yageo")
        (field (name "MPN") "CC0603KRX7R6BB105")
        (field (name "TOLERANCE") "10%")
        (field (name "VOLTAGE") "10V")
      )
      (libsource (lib "eagle-import") (part "CAPACITOR_?_060310V_1UF"))
    )
    (comp (ref "C10")
      (value "CAPACITOR_0603_10V_1UF")
      (footprint "eagle-import:0603-CAP")
      (fields
        (field (name "CAPACITANCE") "1µF")
        (field (name "MANUFACTURER") "Yageo")
        (field (name "MPN") "CC0603KRX7R6BB105")
        (field (name "TOLERANCE") "10%")
        (field (name "VOLTAGE") "10V")
      )
      (libsource (lib "eagle-import") (part "CAPACITOR_?_060310V_1UF"))
    )
    (comp (ref "C11")
      (value "CAPACITOR_0603_10V_1UF")
      (footprint "eagle-import:0603-CAP")
      (fields
        (field (name "CAPACITANCE") "1µF")
        (field (name "MANUFACTURER") "Yageo")
        (field (name "MPN") "CC0603KRX7R6BB105")
        (field (name "TOLERANCE") "10%")
        (field (name "VOLTAGE") "10V")
      )
      (libsource (lib "eagle-import") (part "CAPACITOR_?_060310V_1UF"))
    )
    (comp (ref "C12")
      (value "CAPACITOR_0603_10V_1UF")
      (footprint "eagle-import:0603-CAP")
      (fields
        (field (name "CAPACITANCE") "1µF")
        (field (name "MANUFACTURER") "Yageo")
        (field (name "MPN") "CC0603KRX7R6BB105")
        (field (name "TOLERANCE") "10%")
        (field (name "VOLTAGE") "10V")
      )
      (libsource (lib "eagle-import") (part "CAPACITOR_?_060310V_1UF"))
    )
    (comp (ref "C13")
      (value "CAPACITOR_0603_10V_1UF")
      (footprint "eagle-import:0603-CAP")
      (fields
        (field (name "CAPACITANCE") "1µF")
        (field (name "MANUFACTURER") "Yageo")
        (field (name "MPN") "CC0603KRX7R6BB105")
        (field (name "TOLERANCE") "10%")
        (field (name "VOLTAGE") "10V")
      )
      (libsource (lib "eagle-import") (part "CAPACITOR_?_060310V_1UF"))
    )
    (comp (ref "C14")
      (value "CAPACITOR_0603_10V_1UF")
      (footprint "eagle-import:0603-CAP")
      (fields
        (field (name "CAPACITANCE") "1µF")
        (field (name "MANUFACTURER") "Yageo")
        (field (name "MPN") "CC0603KRX7R6BB105")
        (field (name "TOLERANCE") "10%")
        (field (name "VOLTAGE") "10V")
      )
      (libsource (lib "eagle-import") (part "CAPACITOR_?_060310V_1UF"))
    )
    (comp (ref "C15")
      (value "CAPACITOR_0603_10V_1UF")
      (footprint "eagle-import:0603-CAP")
      (fields
        (field (name "CAPACITANCE") "1µF")
        (field (name "MANUFACTURER") "Yageo")
        (field (name "MPN") "CC0603KRX7R6BB105")
        (field (name "TOLERANCE") "10%")
        (field (name "VOLTAGE") "10V")
      )
      (libsource (lib "eagle-import") (part "CAPACITOR_?_060310V_1UF"))
    )
    (comp (ref "R4")
      (value "RESISTOR_0603_8.35K")
      (footprint "eagle-import:0603-RES")
      (fields
        (field (name "MANUFACTURER") "Vishay Dale Thin Film")
        (field (name "MPN") "PTN0603E8351BST1")
        (field (name "POWER") "0.15W")
        (field (name "RESISTANCE") "8.35k")
      )
      (libsource (lib "eagle-import") (part "RESISTOR_?_06038.35K"))
    )
    (comp (ref "R5")
      (value "RESISTOR_0603_8.35K")
      (footprint "eagle-import:0603-RES")
      (fields
        (field (name "MANUFACTURER") "Vishay Dale Thin Film")
        (field (name "MPN") "PTN0603E8351BST1")
        (field (name "POWER") "0.15W")
        (field (name "RESISTANCE") "8.35k")
      )
      (libsource (lib "eagle-import") (part "RESISTOR_?_06038.35K"))
    )
    (comp (ref "R6")
      (value "RESISTOR_0603_8.35K")
      (footprint "eagle-import:0603-RES")
      (fields
        (field (name "MANUFACTURER") "Vishay Dale Thin Film")
        (field (name "MPN") "PTN0603E8351BST1")
        (field (name "POWER") "0.15W")
        (field (name "RESISTANCE") "8.35k")
      )
      (libsource (lib "eagle-import") (part "RESISTOR_?_06038.35K"))
    )
    (comp (ref "R7")
      (value "RESISTOR_0603_8.35K")
      (footprint "eagle-import:0603-RES")
      (fields
        (field (name "MANUFACTURER") "Vishay Dale Thin Film")
        (field (name "MPN") "PTN0603E8351BST1")
        (field (name "POWER") "0.15W")
        (field (name "RESISTANCE") "8.35k")
      )
      (libsource (lib "eagle-import") (part "RESISTOR_?_06038.35K"))
    )
    (comp (ref "R8")
      (value "RESISTOR_0603_8.35K")
      (footprint "eagle-import:0603-RES")
      (fields
        (field (name "MANUFACTURER") "Vishay Dale Thin Film")
        (field (name "MPN") "PTN0603E8351BST1")
        (field (name "POWER") "0.15W")
        (field (name "RESISTANCE") "8.35k")
      )
      (libsource (lib "eagle-import") (part "RESISTOR_?_06038.35K"))
    )
    (comp (ref "R9")
      (value "RESISTOR_0603_8.35K")
      (footprint "eagle-import:0603-RES")
      (fields
        (field (name "MANUFACTURER") "Vishay Dale Thin Film")
        (field (name "MPN") "PTN0603E8351BST1")
        (field (name "POWER") "0.15W")
        (field (name "RESISTANCE") "8.35k")
      )
      (libsource (lib "eagle-import") (part "RESISTOR_?_06038.35K"))
    )
    (comp (ref "R10")
      (value "RESISTOR_0603_8.35K")
      (footprint "eagle-import:0603-RES")
      (fields
        (field (name "MANUFACTURER") "Vishay Dale Thin Film")
        (field (name "MPN") "PTN0603E8351BST1")
        (field (name "POWER") "0.15W")
        (field (name "RESISTANCE") "8.35k")
      )
      (libsource (lib "eagle-import") (part "RESISTOR_?_06038.35K"))
    )
    (comp (ref "R11")
      (value "RESISTOR_0603_8.35K")
      (footprint "eagle-import:0603-RES")
      (fields
        (field (name "MANUFACTURER") "Vishay Dale Thin Film")
        (field (name "MPN") "PTN0603E8351BST1")
        (field (name "POWER") "0.15W")
        (field (name "RESISTANCE") "8.35k")
      )
      (libsource (lib "eagle-import") (part "RESISTOR_?_06038.35K"))
    )
    (comp (ref "A3")
      (value "TEENSY_4.0SM")
      (footprint "eagle-import:TEENSY_SHORT_SSM")
      (libsource (lib "eagle-import") (part "TEENSY_4.0SM"))
    )
    (comp (ref "C60")
      (value "CAPACITOR_0603_10V_4.7NF")
      (footprint "eagle-import:0603-CAP")
      (fields
        (field (name "CAPACITANCE") "4.7nF")
        (field (name "MANUFACTURER") "Würth Elektronik")
        (field (name "MPN") "885012206012")
        (field (name "TOLERANCE") "10%")
        (field (name "VOLTAGE") "10V")
      )
      (libsource (lib "eagle-import") (part "CAPACITOR_?_060310V_4.7NF"))
    )
    (comp (ref "C61")
      (value "CAPACITOR_0603_10V_4.7UF")
      (footprint "eagle-import:0603-CAP")
      (fields
        (field (name "CAPACITANCE") "4.7µF")
        (field (name "MANUFACTURER") "Samsung Electro-Mechanics")
        (field (name "MPN") "CL10A475KP8NNNC")
        (field (name "TOLERANCE") "10%")
        (field (name "VOLTAGE") "10V")
      )
      (libsource (lib "eagle-import") (part "CAPACITOR_?_060310V_4.7UF"))
    )
    (comp (ref "C62")
      (value "CAPACITOR_0603_35V_0.1UF")
      (footprint "eagle-import:0603-CAP")
      (fields
        (field (name "CAPACITANCE") "0.1µF")
        (field (name "MANUFACTURER") "Taiyo Yuden")
        (field (name "MPN") "GMK107B7104KAHT")
        (field (name "TOLERANCE") "10%")
        (field (name "VOLTAGE") "35V")
      )
      (libsource (lib "eagle-import") (part "CAPACITOR_?_060335V_0.1UF"))
    )
    (comp (ref "C63")
      (value "CAPACITOR_0603_10V_0.1UF")
      (footprint "eagle-import:0603-CAP")
      (fields
        (field (name "CAPACITANCE") "0.1µF")
        (field (name "MANUFACTURER") "Vishay Vitramon")
        (field (name "MPN") "VJ0603Y104JXQPW1BC")
        (field (name "TOLERANCE") "5%")
        (field (name "VOLTAGE") "10V")
      )
      (libsource (lib "eagle-import") (part "CAPACITOR_?_060310V_0.1UF"))
    )
    (comp (ref "C64")
      (value "CAPACITOR_0603_35V_1UF")
      (footprint "eagle-import:0603-CAP")
      (fields
        (field (name "CAPACITANCE") "1µF")
        (field (name "MANUFACTURER") "TDK Corporation")
        (field (name "MPN") "C1608X7R1V105K080AE")
        (field (name "TOLERANCE") "10%")
        (field (name "VOLTAGE") "35V")
      )
      (libsource (lib "eagle-import") (part "CAPACITOR_?_060335V_1UF"))
    )
    (comp (ref "C65")
      (value "CAPACITOR_0603_10V_0.1UF")
      (footprint "eagle-import:0603-CAP")
      (fields
        (field (name "CAPACITANCE") "0.1µF")
        (field (name "MANUFACTURER") "Vishay Vitramon")
        (field (name "MPN") "VJ0603Y104JXQPW1BC")
        (field (name "TOLERANCE") "5%")
        (field (name "VOLTAGE") "10V")
      )
      (libsource (lib "eagle-import") (part "CAPACITOR_?_060310V_0.1UF"))
    )
    (comp (ref "C66")
      (value "CAPACITOR_0603_10V_0.1UF")
      (footprint "eagle-import:0603-CAP")
      (fields
        (field (name "CAPACITANCE") "0.1µF")
        (field (name "MANUFACTURER") "Vishay Vitramon")
        (field (name "MPN") "VJ0603Y104JXQPW1BC")
        (field (name "TOLERANCE") "5%")
        (field (name "VOLTAGE") "10V")
      )
      (libsource (lib "eagle-import") (part "CAPACITOR_?_060310V_0.1UF"))
    )
    (comp (ref "C67")
      (value "CAPACITOR_0603_10V_0.1UF")
      (footprint "eagle-import:0603-CAP")
      (fields
        (field (name "CAPACITANCE") "0.1µF")
        (field (name "MANUFACTURER") "Vishay Vitramon")
        (field (name "MPN") "VJ0603Y104JXQPW1BC")
        (field (name "TOLERANCE") "5%")
        (field (name "VOLTAGE") "10V")
      )
      (libsource (lib "eagle-import") (part "CAPACITOR_?_060310V_0.1UF"))
    )
    (comp (ref "C68")
      (value "CAPACITOR_0603_10V_1UF")
      (footprint "eagle-import:0603-CAP")
      (fields
        (field (name "CAPACITANCE") "1µF")
        (field (name "MANUFACTURER") "Yageo")
        (field (name "MPN") "CC0603KRX7R6BB105")
        (field (name "TOLERANCE") "10%")
        (field (name "VOLTAGE") "10V")
      )
      (libsource (lib "eagle-import") (part "CAPACITOR_?_060310V_1UF"))
    )
    (comp (ref "C69")
      (value "CAPACITOR_0603_10V_1UF")
      (footprint "eagle-import:0603-CAP")
      (fields
        (field (name "CAPACITANCE") "1µF")
        (field (name "MANUFACTURER") "Yageo")
        (field (name "MPN") "CC0603KRX7R6BB105")
        (field (name "TOLERANCE") "10%")
        (field (name "VOLTAGE") "10V")
      )
      (libsource (lib "eagle-import") (part "CAPACITOR_?_060310V_1UF"))
    )
    (comp (ref "CLK")
      (value "TEST_POINT")
      (footprint "eagle-import:5015")
      (fields (field (name "MPN") "5015") (field (name "MANUFACTURER") "Keystone Electronics"))
      (libsource (lib "eagle-import") (part "TEST_POINT"))
    )
    (comp (ref "D8")
      (value "TVS_BIDIRECTIONAL_DUALRS422")
      (footprint "eagle-import:SOT-23")
      (fields (field (name "MPN") "SM712.TCT") (field (name "MANUFACTURER") "Semtech Corporation"))
      (libsource (lib "eagle-import") (part "TVS_BIDIRECTIONAL_DUALRS422"))
    )
    (comp (ref "D9")
      (value "TVS_BIDIRECTIONAL_DUAL")
      (footprint "eagle-import:SC-70-3")
      (fields (field (name "MPN") "TPD2E007DCKR") (field (name "MANUFACTURER") "Texas Instruments"))
      (libsource (lib "eagle-import") (part "TVS_BIDIRECTIONAL_DUAL"))
    )
    (comp (ref "D10")
      (value "TVS_BIDIRECTIONAL_DUALRS422")
      (footprint "eagle-import:SOT-23")
      (fields (field (name "MPN") "SM712.TCT") (field (name "MANUFACTURER") "Semtech Corporation"))
      (libsource (lib "eagle-import") (part "TVS_BIDIRECTIONAL_DUALRS422"))
    )
    (comp (ref "D11")
      (value "TVS_BIDIRECTIONAL_DUAL")
      (footprint "eagle-import:SC-70-3")
      (fields (field (name "MPN") "TPD2E007DCKR") (field (name "MANUFACTURER") "Texas Instruments"))
      (libsource (lib "eagle-import") (part "TVS_BIDIRECTIONAL_DUAL"))
    )
    (comp (ref "D12")
      (value "TVS_BIDIRECTIONAL_DUAL")
      (footprint "eagle-import:SC-70-3")
      (fields (field (name "MPN") "TPD2E007DCKR") (field (name "MANUFACTURER") "Texas Instruments"))
      (libsource (lib "eagle-import") (part "TVS_BIDIRECTIONAL_DUAL"))
    )
    (comp (ref "JP4")
      (value "JUMPER_0603_")
      (footprint "eagle-import:0603-RES")
      (fields (field (name "MPN") "RC0603FR-130RL") (field (name "MANUFACTURER") "YAGEO"))
      (libsource (lib "eagle-import") (part "JUMPER_?_0603"))
    )
    (comp (ref "JP5")
      (value "JUMPER_0603_")
      (footprint "eagle-import:0603-RES")
      (fields (field (name "MPN") "RC0603FR-130RL") (field (name "MANUFACTURER") "YAGEO"))
      (libsource (lib "eagle-import") (part "JUMPER_?_0603"))
    )
    (comp (ref "JP6")
      (value "JUMPER_0603_")
      (footprint "eagle-import:0603-RES")
      (fields (field (name "MPN") "RC0603FR-130RL") (field (name "MANUFACTURER") "YAGEO"))
      (libsource (lib "eagle-import") (part "JUMPER_?_0603"))
    )
    (comp (ref "MISO")
      (value "TEST_POINT")
      (footprint "eagle-import:5015")
      (fields (field (name "MPN") "5015") (field (name "MANUFACTURER") "Keystone Electronics"))
      (libsource (lib "eagle-import") (part "TEST_POINT"))
    )
    (comp (ref "MOSI")
      (value "TEST_POINT")
      (footprint "eagle-import:5015")
      (fields (field (name "MPN") "5015") (field (name "MANUFACTURER") "Keystone Electronics"))
      (libsource (lib "eagle-import") (part "TEST_POINT"))
    )
    (comp (ref "R20")
      (value "RESISTOR_0603_120")
      (footprint "eagle-import:0603-RES")
      (fields
        (field (name "MANUFACTURER") "Panasonic Electronic Components")
        (field (name "MPN") "ERA-3AEB121V")
        (field (name "POWER") "0.1W")
        (field (name "RESISTANCE") "120")
      )
      (libsource (lib "eagle-import") (part "RESISTOR_?_0603120"))
    )
    (comp (ref "R21")
      (value "RESISTOR_0603_60.4")
      (footprint "eagle-import:0603-RES")
      (fields
        (field (name "MANUFACTURER") "Yageo")
        (field (name "MPN") "RC0603FR-0760R4L")
        (field (name "POWER") "0.1W")
        (field (name "RESISTANCE") "60.4")
      )
      (libsource (lib "eagle-import") (part "RESISTOR_?_060360.4"))
    )
    (comp (ref "R22")
      (value "RESISTOR_0603_60.4")
      (footprint "eagle-import:0603-RES")
      (fields
        (field (name "MANUFACTURER") "Yageo")
        (field (name "MPN") "RC0603FR-0760R4L")
        (field (name "POWER") "0.1W")
        (field (name "RESISTANCE") "60.4")
      )
      (libsource (lib "eagle-import") (part "RESISTOR_?_060360.4"))
    )
    (comp (ref "U13")
      (value "TCAN1051HQV-Q1")
      (footprint "eagle-import:SOIC-08(NARROW,0.15_)")
      (fields (field (name "MANUFACTURER") "Texas Instruments") (field (name "MPN") "TCAN1051HGVDRQ1"))
      (libsource (lib "eagle-import") (part "TCAN1051V-Q1HQ"))
    )
    (comp (ref "U14")
      (value "MAX3075")
      (footprint "eagle-import:SOIC-08(NARROW,0.15_)")
      (fields (field (name "MPN") "MAX3075EESA+") (field (name "MANUFACTURER") "Analog Devices Inc."))
      (libsource (lib "eagle-import") (part "MAX3075"))
    )
    (comp (ref "U15")
      (value "MCP3208")
      (footprint "eagle-import:SOIC-16")
      (fields (field (name "MPN") "MCP3208T-BI/SL") (field (name "MANUFACTURER") "Microchip Technology"))
      (libsource (lib "eagle-import") (part "MCP3208"))
    )
  )
  (nets
    (net (code "1") (name "+3V3") (class "Default")
      (node (ref "3V3") (pin "1") (pinfunction "1_1") (pintype "passive"))
      (node (ref "C52") (pin "1") (pinfunction "1_1") (pintype "passive"))
      (node (ref "C53") (pin "1") (pinfunction "1_1") (pintype "passive"))
      (node (ref "C54") (pin "1") (pinfunction "1_1") (pintype "passive"))
      (node (ref "C55") (pin "1") (pinfunction "1_1") (pintype "passive"))
      (node (ref "C56") (pin "1") (pinfunction "1_1") (pintype "passive"))
      (node (ref "C57") (pin "1") (pinfunction "1_1") (pintype "passive"))
      (node (ref "C6") (pin "1") (pinfunction "1_1") (pintype "passive"))
      (node (ref "C62") (pin "1") (pinfunction "1_1") (pintype "passive"))
      (node (ref "C64") (pin "1") (pinfunction "1_1") (pintype "passive"))
      (node (ref "C65") (pin "1") (pinfunction "1_1") (pintype "passive"))
      (node (ref "C66") (pin "1") (pinfunction "1_1") (pintype "passive"))
      (node (ref "C68") (pin "1") (pinfunction "1_1") (pintype "passive"))
      (node (ref "R10") (pin "1") (pinfunction "1_1") (pintype "passive"))
      (node (ref "R11") (pin "1") (pinfunction "1_1") (pintype "passive"))
      (node (ref "R12") (pin "2") (pinfunction "2_2") (pintype "passive"))
      (node (ref "R13") (pin "2") (pinfunction "2_2") (pintype "passive"))
      (node (ref "R3") (pin "1") (pinfunction "1_1") (pintype "passive"))
      (node (ref "R4") (pin "1") (pinfunction "1_1") (pintype "passive"))
      (node (ref "R5") (pin "1") (pinfunction "1_1") (pintype "passive"))
      (node (ref "R6") (pin "1") (pinfunction "1_1") (pintype "passive"))
      (node (ref "R7") (pin "1") (pinfunction "1_1") (pintype "passive"))
      (node (ref "R8") (pin "1") (pinfunction "1_1") (pintype "passive"))
      (node (ref "R9") (pin "1") (pinfunction "1_1") (pintype "passive"))
      (node (ref "U1") (pin "2") (pinfunction "OUT_2") (pintype "power_in"))
      (node (ref "U1") (pin "4") (pinfunction "OUT_4") (pintype "power_in"))
      (node (ref "U10") (pin "12") (pinfunction "FORCEON_12") (pintype "input"))
      (node (ref "U10") (pin "15") (pinfunction "VCC_15") (pintype "power_in"))
      (node (ref "U10") (pin "16") (pinfunction "~{FORCEOFF}_16") (pintype "input"))
      (node (ref "U11") (pin "1") (pinfunction "EN_1") (pintype "passive"))
      (node (ref "U11") (pin "12") (pinfunction "MSTR_12") (pintype "passive"))
      (node (ref "U11") (pin "6") (pinfunction "VLOGIC_6") (pintype "bidirectional"))
      (node (ref "U11") (pin "9") (pinfunction "VDD_9") (pintype "power_in"))
      (node (ref "U12") (pin "1") (pinfunction "EN_1") (pintype "passive"))
      (node (ref "U12") (pin "12") (pinfunction "MSTR_12") (pintype "passive"))
      (node (ref "U12") (pin "6") (pinfunction "VLOGIC_6") (pintype "bidirectional"))
      (node (ref "U12") (pin "9") (pinfunction "VDD_9") (pintype "power_in"))
      (node (ref "U13") (pin "5") (pinfunction "VIO_5") (pintype "power_in"))
      (node (ref "U14") (pin "8") (pinfunction "VCC_8") (pintype "power_in"))
      (node (ref "U15") (pin "15") (pinfunction "VREF_15") (pintype "power_in"))
      (node (ref "U15") (pin "16") (pinfunction "VDD_16") (pintype "power_in"))
    )
    (net (code "2") (name "+5V") (class "Default")
      (node (ref "5V") (pin "1") (pinfunction "1_1") (pintype "passive"))
      (node (ref "A2") (pin "3") (pinfunction "OUT_3") (pintype "power_in"))
      (node (ref "A3") (pin "VIN") (pinfunction "VIN_VIN") (pintype "power_in"))
      (node (ref "C3") (pin "1") (pinfunction "1_1") (pintype "passive"))
      (node (ref "C5") (pin "1") (pinfunction "1_1") (pintype "passive"))
      (node (ref "C61") (pin "1") (pinfunction "1_1") (pintype "passive"))
      (node (ref "C63") (pin "1") (pinfunction "1_1") (pintype "passive"))
      (node (ref "C67") (pin "1") (pinfunction "1_1") (pintype "passive"))
      (node (ref "C69") (pin "1") (pinfunction "1_1") (pintype "passive"))
      (node (ref "J14") (pin "3") (pinfunction "3_3") (pintype "passive"))
      (node (ref "J16") (pin "3") (pinfunction "3_3") (pintype "passive"))
      (node (ref "JP5V") (pin "2") (pinfunction "2_2") (pintype "passive"))
      (node (ref "R2") (pin "1") (pinfunction "1_1") (pintype "passive"))
      (node (ref "U1") (pin "3") (pinfunction "IN_3") (pintype "power_in"))
      (node (ref "U13") (pin "3") (pinfunction "VDD_3") (pintype "power_in"))
    )
    (net (code "3") (name "+12V") (class "Default")
      (node (ref "12V") (pin "1") (pinfunction "1_1") (pintype "passive"))
      (node (ref "A1") (pin "3") (pinfunction "OUT_3") (pintype "power_in"))
      (node (ref "C4") (pin "1") (pinfunction "1_1") (pintype "passive"))
      (node (ref "D4") (pin "P$2") (pinfunction "C_P$2") (pintype "passive"))
      (node (ref "J10") (pin "1") (pinfunction "1_1") (pintype "passive"))
      (node (ref "J2") (pin "1") (pinfunction "1_1") (pintype "passive"))
      (node (ref "J3") (pin "1") (pinfunction "1_1") (pintype "passive"))
      (node (ref "J4") (pin "1") (pinfunction "1_1") (pintype "passive"))
      (node (ref "J5") (pin "1") (pinfunction "1_1") (pintype "passive"))
      (node (ref "J7") (pin "1") (pinfunction "1_1") (pintype "passive"))
      (node (ref "J9") (pin "1") (pinfunction "1_1") (pintype "passive"))
      (node (ref "JP12V") (pin "2") (pinfunction "2_2") (pintype "passive"))
      (node (ref "R1") (pin "1") (pinfunction "1_1") (pintype "passive"))
    )
    (net (code "4") (name "+24V") (class "Default")
      (node (ref "A1") (pin "1") (pinfunction "IN_1") (pintype "power_in"))
      (node (ref "A2") (pin "1") (pinfunction "IN_1") (pintype "power_in"))
      (node (ref "C1") (pin "1") (pinfunction "1_1") (pintype "passive"))
      (node (ref "C2") (pin "1") (pinfunction "1_1") (pintype "passive"))
      (node (ref "C7") (pin "PLUS") (pinfunction "PLUS_PLUS") (pintype "passive"))
      (node (ref "J12") (pin "1") (pinfunction "1_1") (pintype "passive"))
      (node (ref "J14") (pin "4") (pinfunction "4_4") (pintype "passive"))
      (node (ref "J15") (pin "1") (pinfunction "1_1") (pintype "passive"))
      (node (ref "J16") (pin "4") (pinfunction "4_4") (pintype "passive"))
      (node (ref "JP24V") (pin "2") (pinfunction "2_2") (pintype "passive"))
      (node (ref "XF1") (pin "3") (pinfunction "2_3") (pintype "passive"))
      (node (ref "XF1") (pin "4") (pinfunction "2_4") (pintype "passive"))
    )
    (net (code "5") (name "3.3V") (class "Default")
      (node (ref "A3") (pin "3.3V") (pinfunction "3.3V_3.3V") (pintype "power_in"))
    )
    (net (code "6") (name "24VIN") (class "Default")
      (node (ref "D6") (pin "2") (pinfunction "C_2") (pintype "passive"))
      (node (ref "J11") (pin "1") (pinfunction "1_1") (pintype "passive"))
      (node (ref "XF1") (pin "1") (pinfunction "1_1") (pintype "passive"))
      (node (ref "XF1") (pin "2") (pinfunction "1_2") (pintype "passive"))
    )
    (net (code "7") (name "CAN_N") (class "Default")
      (node (ref "CAN_L") (pin "1") (pinfunction "1_1") (pintype "passive"))
      (node (ref "D11") (pin "2") (pinfunction "C2_2") (pintype "passive"))
      (node (ref "D12") (pin "2") (pinfunction "C2_2") (pintype "passive"))
      (node (ref "D9") (pin "2") (pinfunction "C2_2") (pintype "passive"))
      (node (ref "J12") (pin "3") (pinfunction "3_3") (pintype "passive"))
      (node (ref "J13") (pin "3") (pinfunction "3_3") (pintype "passive"))
      (node (ref "J15") (pin "3") (pinfunction "3_3") (pintype "passive"))
      (node (ref "J4") (pin "3") (pinfunction "3_3") (pintype "passive"))
      (node (ref "J5") (pin "3") (pinfunction "3_3") (pintype "passive"))
      (node (ref "J9") (pin "3") (pinfunction "3_3") (pintype "passive"))
      (node (ref "JP4") (pin "1") (pinfunction "1_1") (pintype "passive"))
      (node (ref "U13") (pin "6") (pinfunction "CANL_6") (pintype "bidirectional"))
    )
    (net (code "8") (name "CAN_P") (class "Default")
      (node (ref "CAN_H") (pin "1") (pinfunction "1_1") (pintype "passive"))
      (node (ref "D11") (pin "1") (pinfunction "C1_1") (pintype "passive"))
      (node (ref "D12") (pin "1") (pinfunction "C1_1") (pintype "passive"))
      (node (ref "D9") (pin "1") (pinfunction "C1_1") (pintype "passive"))
      (node (ref "J12") (pin "2") (pinfunction "2_2") (pintype "passive"))
      (node (ref "J13") (pin "2") (pinfunction "2_2") (pintype "passive"))
      (node (ref "J15") (pin "2") (pinfunction "2_2") (pintype "passive"))
      (node (ref "J4") (pin "4") (pinfunction "4_4") (pintype "passive"))
      (node (ref "J5") (pin "4") (pinfunction "4_4") (pintype "passive"))
      (node (ref "J9") (pin "4") (pinfunction "4_4") (pintype "passive"))
      (node (ref "JP6") (pin "2") (pinfunction "2_2") (pintype "passive"))
      (node (ref "U13") (pin "7") (pinfunction "CANH_7") (pintype "output"))
    )
    (net (code "9") (name "EN_485") (class "Default")
      (node (ref "A3") (pin "D18") (pinfunction "A4_D18") (pintype "bidirectional"))
      (node (ref "U14") (pin "2") (pinfunction "~{RE}_2") (pintype "input"))
      (node (ref "U14") (pin "3") (pinfunction "DE_3") (pintype "input"))
    )
    (net (code "10") (name "GND") (class "Default")
      (node (ref "A1") (pin "2") (pinfunction "GND_2") (pintype "power_in"))
      (node (ref "A2") (pin "2") (pinfunction "GND_2") (pintype "power_in"))
      (node (ref "A3") (pin "AGND/GND") (pinfunction "GND_AGND/GND") (pintype "power_in"))
      (node (ref "A3") (pin "GND") (pinfunction "GND_GND") (pintype "power_in"))
      (node (ref "C1") (pin "2") (pinfunction "2_2") (pintype "passive"))
      (node (ref "C10") (pin "2") (pinfunction "2_2") (pintype "passive"))
      (node (ref "C11") (pin "2") (pinfunction "2_2") (pintype "passive"))
      (node (ref "C12") (pin "2") (pinfunction "2_2") (pintype "passive"))
      (node (ref "C13") (pin "2") (pinfunction "2_2") (pintype "passive"))
      (node (ref "C14") (pin "2") (pinfunction "2_2") (pintype "passive"))
      (node (ref "C15") (pin "2") (pinfunction "2_2") (pintype "passive"))
      (node (ref "C2") (pin "2") (pinfunction "2_2") (pintype "passive"))
      (node (ref "C3") (pin "2") (pinfunction "2_2") (pintype "passive"))
      (node (ref "C4") (pin "2") (pinfunction "2_2") (pintype "passive"))
      (node (ref "C5") (pin "2") (pinfunction "2_2") (pintype "passive"))
      (node (ref "C50") (pin "1") (pinfunction "1_1") (pintype "passive"))
      (node (ref "C51") (pin "1") (pinfunction "1_1") (pintype "passive"))
      (node (ref "C52") (pin "2") (pinfunction "2_2") (pintype "passive"))
      (node (ref "C53") (pin "2") (pinfunction "2_2") (pintype "passive"))
      (node (ref "C54") (pin "2") (pinfunction "2_2") (pintype "passive"))
      (node (ref "C55") (pin "2") (pinfunction "2_2") (pintype "passive"))
      (node (ref "C56") (pin "2") (pinfunction "2_2") (pintype "passive"))
      (node (ref "C57") (pin "2") (pinfunction "2_2") (pintype "passive"))
      (node (ref "C58") (pin "2") (pinfunction "2_2") (pintype "passive"))
      (node (ref "C59") (pin "2") (pinfunction "2_2") (pintype "passive"))
      (node (ref "C6") (pin "2") (pinfunction "2_2") (pintype "passive"))
      (node (ref "C60") (pin "2") (pinfunction "2_2") (pintype "passive"))
      (node (ref "C61") (pin "2") (pinfunction "2_2") (pintype "passive"))
      (node (ref "C62") (pin "2") (pinfunction "2_2") (pintype "passive"))
      (node (ref "C63") (pin "2") (pinfunction "2_2") (pintype "passive"))
      (node (ref "C64") (pin "2") (pinfunction "2_2") (pintype "passive"))
      (node (ref "C65") (pin "2") (pinfunction "2_2") (pintype "passive"))
      (node (ref "C66") (pin "2") (pinfunction "2_2") (pintype "passive"))
      (node (ref "C67") (pin "2") (pinfunction "2_2") (pintype "passive"))
      (node (ref "C68") (pin "2") (pinfunction "2_2") (pintype "passive"))
      (node (ref "C69") (pin "2") (pinfunction "2_2") (pintype "passive"))
      (node (ref "C7") (pin "MINUS") (pinfunction "MINUS_MINUS") (pintype "passive"))
      (node (ref "C8") (pin "2") (pinfunction "2_2") (pintype "passive"))
      (node (ref "C9") (pin "2") (pinfunction "2_2") (pintype "passive"))
      (node (ref "D1") (pin "1") (pinfunction "C_1") (pintype "passive"))
      (node (ref "D10") (pin "3") (pinfunction "A_3") (pintype "passive"))
      (node (ref "D11") (pin "3") (pinfunction "A_3") (pintype "passive"))
      (node (ref "D12") (pin "3") (pinfunction "A_3") (pintype "passive"))
      (node (ref "D2") (pin "1") (pinfunction "C_1") (pintype "passive"))
      (node (ref "D3") (pin "1") (pinfunction "C_1") (pintype "passive"))
      (node (ref "D4") (pin "P$1") (pinfunction "A_P$1") (pintype "passive"))
      (node (ref "D6") (pin "1") (pinfunction "A_1") (pintype "passive"))
      (node (ref "D7") (pin "3") (pinfunction "A_3") (pintype "passive"))
      (node (ref "D8") (pin "3") (pinfunction "A_3") (pintype "passive"))
      (node (ref "D9") (pin "3") (pinfunction "A_3") (pintype "passive"))
      (node (ref "GND") (pin "1") (pinfunction "1_1") (pintype "passive"))
      (node (ref "J1") (pin "1") (pinfunction "1_1") (pintype "passive"))
      (node (ref "J1") (pin "2") (pinfunction "2_2") (pintype "passive"))
      (node (ref "J1") (pin "3") (pinfunction "3_3") (pintype "passive"))
      (node (ref "J1") (pin "4") (pinfunction "4_4") (pintype "passive"))
      (node (ref "J10") (pin "5") (pinfunction "5_5") (pintype "passive"))
      (node (ref "J11") (pin "2") (pinfunction "2_2") (pintype "passive"))
      (node (ref "J12") (pin "6") (pinfunction "6_6") (pintype "passive"))
      (node (ref "J13") (pin "4") (pinfunction "4_4") (pintype "passive"))
      (node (ref "J14") (pin "1") (pinfunction "1_1") (pintype "passive"))
      (node (ref "J15") (pin "4") (pinfunction "4_4") (pintype "passive"))
      (node (ref "J16") (pin "1") (pinfunction "1_1") (pintype "passive"))
      (node (ref "J2") (pin "2") (pinfunction "2_2") (pintype "passive"))
      (node (ref "J3") (pin "2") (pinfunction "2_2") (pintype "passive"))
      (node (ref "J4") (pin "2") (pinfunction "2_2") (pintype "passive"))
      (node (ref "J5") (pin "2") (pinfunction "2_2") (pintype "passive"))
      (node (ref "J6") (pin "1") (pinfunction "1_1") (pintype "passive"))
      (node (ref "J6") (pin "2") (pinfunction "2_2") (pintype "passive"))
      (node (ref "J6") (pin "3") (pinfunction "3_3") (pintype "passive"))
      (node (ref "J6") (pin "4") (pinfunction "4_4") (pintype "passive"))
      (node (ref "J7") (pin "2") (pinfunction "2_2") (pintype "passive"))
      (node (ref "J8") (pin "2") (pinfunction "2_2") (pintype "passive"))
      (node (ref "J9") (pin "2") (pinfunction "2_2") (pintype "passive"))
      (node (ref "R15") (pin "1") (pinfunction "1_1") (pintype "passive"))
      (node (ref "R17") (pin "1") (pinfunction "1_1") (pintype "passive"))
      (node (ref "U1") (pin "1") (pinfunction "GND_1") (pintype "power_in"))
      (node (ref "U10") (pin "14") (pinfunction "GND_14") (pintype "power_in"))
      (node (ref "U11") (pin "13") (pinfunction "SLOW_13") (pintype "passive"))
      (node (ref "U11") (pin "14") (pinfunction "GND_14") (pintype "power_in"))
      (node (ref "U11") (pin "7") (pinfunction "POL_7") (pintype "passive"))
      (node (ref "U11") (pin "8") (pinfunction "PHA_8") (pintype "passive"))
      (node (ref "U12") (pin "13") (pinfunction "SLOW_13") (pintype "passive"))
      (node (ref "U12") (pin "14") (pinfunction "GND_14") (pintype "power_in"))
      (node (ref "U12") (pin "7") (pinfunction "POL_7") (pintype "passive"))
      (node (ref "U12") (pin "8") (pinfunction "PHA_8") (pintype "passive"))
      (node (ref "U13") (pin "2") (pinfunction "GND_2") (pintype "power_in"))
      (node (ref "U13") (pin "8") (pinfunction "S_8") (pintype "input"))
      (node (ref "U14") (pin "5") (pinfunction "GND_5") (pintype "power_in"))
      (node (ref "U15") (pin "14") (pinfunction "AGND_14") (pintype "power_in"))
      (node (ref "U15") (pin "9") (pinfunction "GND_9") (pintype "power_in"))
    )
    (net (code "11") (name "GPS_PPS") (class "Default")
      (node (ref "A3") (pin "D4") (pinfunction "D4_D4") (pintype "bidirectional"))
      (node (ref "J10") (pin "10") (pinfunction "10_10") (pintype "passive"))
    )
    (net (code "12") (name "Net-(C60-Pad1)") (class "Default")
      (node (ref "C60") (pin "1") (pinfunction "1_1") (pintype "passive"))
      (node (ref "R21") (pin "2") (pinfunction "2_2") (pintype "passive"))
      (node (ref "R22") (pin "1") (pinfunction "1_1") (pintype "passive"))
    )
    (net (code "13") (name "Net-(D1-A)") (class "Default")
      (node (ref "D1") (pin "2") (pinfunction "A_2") (pintype "passive"))
      (node (ref "R1") (pin "2") (pinfunction "2_2") (pintype "passive"))
    )
    (net (code "14") (name "Net-(D2-A)") (class "Default")
      (node (ref "D2") (pin "2") (pinfunction "A_2") (pintype "passive"))
      (node (ref "R2") (pin "2") (pinfunction "2_2") (pintype "passive"))
    )
    (net (code "15") (name "Net-(D3-A)") (class "Default")
      (node (ref "D3") (pin "2") (pinfunction "A_2") (pintype "passive"))
      (node (ref "R3") (pin "2") (pinfunction "2_2") (pintype "passive"))
    )
    (net (code "16") (name "Net-(J13-Pad1)") (class "Default")
      (node (ref "J13") (pin "1") (pinfunction "1_1") (pintype "passive"))
      (node (ref "JP12V") (pin "1") (pinfunction "1_1") (pintype "passive"))
      (node (ref "JP24V") (pin "1") (pinfunction "1_1") (pintype "passive"))
      (node (ref "JP5V") (pin "1") (pinfunction "1_1") (pintype "passive"))
    )
    (net (code "17") (name "Net-(JP4-Pad2)") (class "Default")
      (node (ref "JP4") (pin "2") (pinfunction "2_2") (pintype "passive"))
      (node (ref "R21") (pin "1") (pinfunction "1_1") (pintype "passive"))
    )
    (net (code "18") (name "Net-(JP5-Pad1)") (class "Default")
      (node (ref "JP5") (pin "1") (pinfunction "1_1") (pintype "passive"))
      (node (ref "R20") (pin "2") (pinfunction "2_2") (pintype "passive"))
    )
    (net (code "19") (name "Net-(JP6-Pad1)") (class "Default")
      (node (ref "JP6") (pin "1") (pinfunction "1_1") (pintype "passive"))
      (node (ref "R22") (pin "2") (pinfunction "2_2") (pintype "passive"))
    )
    (net (code "20") (name "Net-(T1-PRI_CENTER_TAP)") (class "Default")
      (node (ref "C58") (pin "1") (pinfunction "1_1") (pintype "passive"))
      (node (ref "T1") (pin "2") (pinfunction "PRI_CENTER_TAP_2") (pintype "passive"))
    )
    (net (code "21") (name "Net-(T2-PRI_CENTER_TAP)") (class "Default")
      (node (ref "C59") (pin "1") (pinfunction "1_1") (pintype "passive"))
      (node (ref "T2") (pin "2") (pinfunction "PRI_CENTER_TAP_2") (pintype "passive"))
    )
    (net (code "22") (name "Net-(U10-C1+)") (class "Default")
      (node (ref "C48") (pin "1") (pinfunction "1_1") (pintype "passive"))
      (node (ref "U10") (pin "2") (pinfunction "C1+_2") (pintype "passive"))
    )
    (net (code "23") (name "Net-(U10-C1-)") (class "Default")
      (node (ref "C48") (pin "2") (pinfunction "2_2") (pintype "passive"))
      (node (ref "U10") (pin "4") (pinfunction "C1-_4") (pintype "passive"))
    )
    (net (code "24") (name "Net-(U10-C2+)") (class "Default")
      (node (ref "C49") (pin "1") (pinfunction "1_1") (pintype "passive"))
      (node (ref "U10") (pin "5") (pinfunction "C2+_5") (pintype "passive"))
    )
    (net (code "25") (name "Net-(U10-C2-)") (class "Default")
      (node (ref "C49") (pin "2") (pinfunction "2_2") (pintype "passive"))
      (node (ref "U10") (pin "6") (pinfunction "C2-_6") (pintype "passive"))
    )
    (net (code "26") (name "Net-(U10-V+)") (class "Default")
      (node (ref "C50") (pin "2") (pinfunction "2_2") (pintype "passive"))
      (node (ref "U10") (pin "3") (pinfunction "V+_3") (pintype "bidirectional"))
    )
    (net (code "27") (name "Net-(U10-V-)") (class "Default")
      (node (ref "C51") (pin "2") (pinfunction "2_2") (pintype "passive"))
      (node (ref "U10") (pin "7") (pinfunction "V-_7") (pintype "bidirectional"))
    )
    (net (code "28") (name "Net-(U11-IBIAS)") (class "Default")
      (node (ref "R14") (pin "2") (pinfunction "2_2") (pintype "passive"))
      (node (ref "U11") (pin "16") (pinfunction "IBIAS_16") (pintype "bidirectional"))
    )
    (net (code "29") (name "Net-(U11-ICMP)") (class "Default")
      (node (ref "R14") (pin "1") (pinfunction "1_1") (pintype "passive"))
      (node (ref "R15") (pin "2") (pinfunction "2_2") (pintype "passive"))
      (node (ref "U11") (pin "15") (pinfunction "ICMP_15") (pintype "bidirectional"))
    )
    (net (code "30") (name "Net-(U12-IBIAS)") (class "Default")
      (node (ref "R16") (pin "2") (pinfunction "2_2") (pintype "passive"))
      (node (ref "U12") (pin "16") (pinfunction "IBIAS_16") (pintype "bidirectional"))
    )
    (net (code "31") (name "Net-(U12-ICMP)") (class "Default")
      (node (ref "R16") (pin "1") (pinfunction "1_1") (pintype "passive"))
      (node (ref "R17") (pin "2") (pinfunction "2_2") (pintype "passive"))
      (node (ref "U12") (pin "15") (pinfunction "ICMP_15") (pintype "bidirectional"))
    )
    (net (code "32") (name "PI_SHUTDOWN") (class "Default")
      (node (ref "A3") (pin "D14") (pinfunction "A0_D14") (pintype "bidirectional"))
      (node (ref "J8") (pin "1") (pinfunction "1_1") (pintype "passive"))
    )
    (net (code "33") (name "RESTORE") (class "Default")
      (node (ref "A3") (pin "D9") (pinfunction "D9_D9") (pintype "bidirectional"))
      (node (ref "J10") (pin "6") (pinfunction "6_6") (pintype "passive"))
    )
    (net (code "34") (name "RHEIGHT_N") (class "Default")
      (node (ref "D10") (pin "2") (pinfunction "C2_2") (pintype "passive"))
      (node (ref "D8") (pin "2") (pinfunction "C2_2") (pintype "passive"))
      (node (ref "J2") (pin "3") (pinfunction "3_3") (pintype "passive"))
      (node (ref "J3") (pin "3") (pinfunction "3_3") (pintype "passive"))
      (node (ref "J7") (pin "3") (pinfunction "3_3") (pintype "passive"))
      (node (ref "JP5") (pin "2") (pinfunction "2_2") (pintype "passive"))
      (node (ref "RH_N") (pin "1") (pinfunction "1_1") (pintype "passive"))
      (node (ref "U14") (pin "7") (pinfunction "B_7") (pintype "bidirectional"))
    )
    (net (code "35") (name "RHEIGHT_P") (class "Default")
      (node (ref "D10") (pin "1") (pinfunction "C1_1") (pintype "passive"))
      (node (ref "D8") (pin "1") (pinfunction "C1_1") (pintype "passive"))
      (node (ref "J2") (pin "4") (pinfunction "4_4") (pintype "passive"))
      (node (ref "J3") (pin "4") (pinfunction "4_4") (pintype "passive"))
      (node (ref "J7") (pin "4") (pinfunction "4_4") (pintype "passive"))
      (node (ref "R20") (pin "1") (pinfunction "1_1") (pintype "passive"))
      (node (ref "RH_P") (pin "1") (pinfunction "1_1") (pintype "passive"))
      (node (ref "U14") (pin "6") (pinfunction "A_6") (pintype "bidirectional"))
    )
    (net (code "36") (name "RL_EXT_N") (class "Default")
      (node (ref "J14") (pin "6") (pinfunction "6_6") (pintype "passive"))
      (node (ref "T1") (pin "4") (pinfunction "SEC_1_4") (pintype "passive"))
    )
    (net (code "37") (name "RL_EXT_P") (class "Default")
      (node (ref "J14") (pin "5") (pinfunction "5_5") (pintype "passive"))
      (node (ref "T1") (pin "6") (pinfunction "SEC_2_6") (pintype "passive"))
    )
    (net (code "38") (name "RL_N") (class "Default")
      (node (ref "R18") (pin "1") (pinfunction "1_1") (pintype "passive"))
      (node (ref "RL_IM") (pin "1") (pinfunction "1_1") (pintype "passive"))
      (node (ref "T1") (pin "3") (pinfunction "PRI_2_3") (pintype "passive"))
      (node (ref "U11") (pin "10") (pinfunction "IM_10") (pintype "bidirectional"))
    )
    (net (code "39") (name "RL_P") (class "Default")
      (node (ref "R18") (pin "2") (pinfunction "2_2") (pintype "passive"))
      (node (ref "RL_IP") (pin "1") (pinfunction "1_1") (pintype "passive"))
      (node (ref "T1") (pin "1") (pinfunction "PRI_1_1") (pintype "passive"))
      (node (ref "U11") (pin "11") (pinfunction "IP_11") (pintype "bidirectional"))
    )
    (net (code "40") (name "RR_EXT_N") (class "Default")
      (node (ref "J16") (pin "6") (pinfunction "6_6") (pintype "passive"))
      (node (ref "T2") (pin "4") (pinfunction "SEC_1_4") (pintype "passive"))
    )
    (net (code "41") (name "RR_EXT_P") (class "Default")
      (node (ref "J16") (pin "5") (pinfunction "5_5") (pintype "passive"))
      (node (ref "T2") (pin "6") (pinfunction "SEC_2_6") (pintype "passive"))
    )
    (net (code "42") (name "RR_N") (class "Default")
      (node (ref "R19") (pin "1") (pinfunction "1_1") (pintype "passive"))
      (node (ref "RR_IM") (pin "1") (pinfunction "1_1") (pintype "passive"))
      (node (ref "T2") (pin "3") (pinfunction "PRI_2_3") (pintype "passive"))
      (node (ref "U12") (pin "10") (pinfunction "IM_10") (pintype "bidirectional"))
    )
    (net (code "43") (name "RR_P") (class "Default")
      (node (ref "R19") (pin "2") (pinfunction "2_2") (pintype "passive"))
      (node (ref "RR_IP") (pin "1") (pinfunction "1_1") (pintype "passive"))
      (node (ref "T2") (pin "1") (pinfunction "PRI_1_1") (pintype "passive"))
      (node (ref "U12") (pin "11") (pinfunction "IP_11") (pintype "bidirectional"))
    )
    (net (code "44") (name "RXD_232") (class "Default")
      (node (ref "D7") (pin "2") (pinfunction "C2_2") (pintype "passive"))
      (node (ref "J10") (pin "2") (pinfunction "2_2") (pintype "passive"))
      (node (ref "RXD") (pin "1") (pinfunction "1_1") (pintype "passive"))
      (node (ref "U10") (pin "8") (pinfunction "R1IN_8") (pintype "input"))
    )
    (net (code "45") (name "RX_232") (class "Default")
      (node (ref "A3") (pin "D7") (pinfunction "D7_D7") (pintype "bidirectional"))
      (node (ref "U10") (pin "9") (pinfunction "R1OUT_9") (pintype "output"))
    )
    (net (code "46") (name "RX_485") (class "Default")
      (node (ref "A3") (pin "D16") (pinfunction "A2_D16") (pintype "bidirectional"))
      (node (ref "U14") (pin "1") (pinfunction "RO_1") (pintype "output"))
    )
    (net (code "47") (name "SHDN_K") (class "Default")
      (node (ref "J12") (pin "4") (pinfunction "4_4") (pintype "passive"))
      (node (ref "J14") (pin "7") (pinfunction "7_7") (pintype "passive"))
    )
    (net (code "48") (name "SHDN_L") (class "Default")
      (node (ref "J14") (pin "8") (pinfunction "8_8") (pintype "passive"))
      (node (ref "J16") (pin "7") (pinfunction "7_7") (pintype "passive"))
    )
    (net (code "49") (name "SHDN_M") (class "Default")
      (node (ref "J12") (pin "5") (pinfunction "5_5") (pintype "passive"))
      (node (ref "J16") (pin "2") (pinfunction "2_2") (pintype "passive"))
    )
    (net (code "50") (name "SYNC_IN") (class "Default")
      (node (ref "A3") (pin "D6") (pinfunction "D6_D6") (pintype "bidirectional"))
      (node (ref "J10") (pin "7") (pinfunction "7_7") (pintype "passive"))
    )
    (net (code "51") (name "SYNC_OUT") (class "Default")
      (node (ref "A3") (pin "D5") (pinfunction "D5_D5") (pintype "bidirectional"))
      (node (ref "J10") (pin "4") (pinfunction "4_4") (pintype "passive"))
    )
    (net (code "52") (name "TEENSY_CAN_RX1") (class "Default")
      (node (ref "A3") (pin "D0") (pinfunction "(CRX1)D0_D0") (pintype "bidirectional"))
      (node (ref "U13") (pin "4") (pinfunction "RXD_4") (pintype "output"))
    )
    (net (code "53") (name "TEENSY_CAN_TX1") (class "Default")
      (node (ref "A3") (pin "D1") (pinfunction "(CTX1)D1_D1") (pintype "bidirectional"))
      (node (ref "U13") (pin "1") (pinfunction "TXD_1") (pintype "input"))
    )
    (net (code "54") (name "TEENSY_CLK") (class "Default")
      (node (ref "A3") (pin "D13") (pinfunction "(CLK)D13_D13") (pintype "bidirectional"))
      (node (ref "CLK") (pin "1") (pinfunction "1_1") (pintype "passive"))
      (node (ref "U11") (pin "4") (pinfunction "CLK_4") (pintype "input"))
      (node (ref "U12") (pin "4") (pinfunction "CLK_4") (pintype "input"))
      (node (ref "U15") (pin "13") (pinfunction "CLK_13") (pintype "input"))
    )
    (net (code "55") (name "TEENSY_SDI") (class "Default")
      (node (ref "A3") (pin "D12") (pinfunction "(SDI)D12_D12") (pintype "bidirectional"))
      (node (ref "MISO") (pin "1") (pinfunction "1_1") (pintype "passive"))
      (node (ref "R12") (pin "1") (pinfunction "1_1") (pintype "passive"))
      (node (ref "R13") (pin "1") (pinfunction "1_1") (pintype "passive"))
      (node (ref "U11") (pin "3") (pinfunction "SDO_3") (pintype "open_collector"))
      (node (ref "U12") (pin "3") (pinfunction "SDO_3") (pintype "open_collector"))
      (node (ref "U15") (pin "12") (pinfunction "SDO_12") (pintype "output"))
    )
    (net (code "56") (name "TEENSY_SDO") (class "Default")
      (node (ref "A3") (pin "D11") (pinfunction "(SDO)D11_D11") (pintype "bidirectional"))
      (node (ref "MOSI") (pin "1") (pinfunction "1_1") (pintype "passive"))
      (node (ref "U11") (pin "2") (pinfunction "SDI_2") (pintype "open_collector"))
      (node (ref "U12") (pin "2") (pinfunction "SDI_2") (pintype "open_collector"))
      (node (ref "U15") (pin "11") (pinfunction "SDI_11") (pintype "input"))
    )
    (net (code "57") (name "THERM1") (class "Default")
      (node (ref "C8") (pin "1") (pinfunction "1_1") (pintype "passive"))
      (node (ref "J6") (pin "8") (pinfunction "8_8") (pintype "passive"))
      (node (ref "R4") (pin "2") (pinfunction "2_2") (pintype "passive"))
      (node (ref "U15") (pin "1") (pinfunction "CH0_1") (pintype "input"))
    )
    (net (code "58") (name "THERM2") (class "Default")
      (node (ref "C9") (pin "1") (pinfunction "1_1") (pintype "passive"))
      (node (ref "J6") (pin "7") (pinfunction "7_7") (pintype "passive"))
      (node (ref "R5") (pin "2") (pinfunction "2_2") (pintype "passive"))
      (node (ref "U15") (pin "2") (pinfunction "CH1_2") (pintype "input"))
    )
    (net (code "59") (name "THERM3") (class "Default")
      (node (ref "C10") (pin "1") (pinfunction "1_1") (pintype "passive"))
      (node (ref "J6") (pin "6") (pinfunction "6_6") (pintype "passive"))
      (node (ref "R6") (pin "2") (pinfunction "2_2") (pintype "passive"))
      (node (ref "U15") (pin "3") (pinfunction "CH2_3") (pintype "input"))
    )
    (net (code "60") (name "THERM4") (class "Default")
      (node (ref "C11") (pin "1") (pinfunction "1_1") (pintype "passive"))
      (node (ref "J6") (pin "5") (pinfunction "5_5") (pintype "passive"))
      (node (ref "R7") (pin "2") (pinfunction "2_2") (pintype "passive"))
      (node (ref "U15") (pin "4") (pinfunction "CH3_4") (pintype "input"))
    )
    (net (code "61") (name "THERM5") (class "Default")
      (node (ref "C12") (pin "1") (pinfunction "1_1") (pintype "passive"))
      (node (ref "J1") (pin "8") (pinfunction "8_8") (pintype "passive"))
      (node (ref "R8") (pin "2") (pinfunction "2_2") (pintype "passive"))
      (node (ref "U15") (pin "5") (pinfunction "CH4_5") (pintype "input"))
    )
    (net (code "62") (name "THERM6") (class "Default")
      (node (ref "C13") (pin "1") (pinfunction "1_1") (pintype "passive"))
      (node (ref "J1") (pin "7") (pinfunction "7_7") (pintype "passive"))
      (node (ref "R9") (pin "2") (pinfunction "2_2") (pintype "passive"))
      (node (ref "U15") (pin "6") (pinfunction "CH5_6") (pintype "input"))
    )
    (net (code "63") (name "THERM7") (class "Default")
      (node (ref "C14") (pin "1") (pinfunction "1_1") (pintype "passive"))
      (node (ref "J1") (pin "6") (pinfunction "6_6") (pintype "passive"))
      (node (ref "R10") (pin "2") (pinfunction "2_2") (pintype "passive"))
      (node (ref "U15") (pin "7") (pinfunction "CH6_7") (pintype "input"))
    )
    (net (code "64") (name "THERM8") (class "Default")
      (node (ref "C15") (pin "1") (pinfunction "1_1") (pintype "passive"))
      (node (ref "J1") (pin "5") (pinfunction "5_5") (pintype "passive"))
      (node (ref "R11") (pin "2") (pinfunction "2_2") (pintype "passive"))
      (node (ref "U15") (pin "8") (pinfunction "CH7_8") (pintype "input"))
    )
    (net (code "65") (name "TXD_232") (class "Default")
      (node (ref "D7") (pin "1") (pinfunction "C1_1") (pintype "passive"))
      (node (ref "J10") (pin "3") (pinfunction "3_3") (pintype "passive"))
      (node (ref "TXD") (pin "1") (pinfunction "1_1") (pintype "passive"))
      (node (ref "U10") (pin "13") (pinfunction "T1OUT_13") (pintype "output"))
    )
    (net (code "66") (name "TX_232") (class "Default")
      (node (ref "A3") (pin "D8") (pinfunction "D8_D8") (pintype "bidirectional"))
      (node (ref "U10") (pin "11") (pinfunction "T1IN_11") (pintype "input"))
    )
    (net (code "67") (name "TX_485") (class "Default")
      (node (ref "A3") (pin "D17") (pinfunction "A3_D17") (pintype "bidirectional"))
      (node (ref "U14") (pin "4") (pinfunction "DI_4") (pintype "input"))
    )
    (net (code "68") (name "unconnected-(A3-A1-PadD15)") (class "Default")
      (node (ref "A3") (pin "D15") (pinfunction "A1_D15") (pintype "bidirectional"))
    )
    (net (code "69") (name "unconnected-(A3-A5-PadD19)") (class "Default")
      (node (ref "A3") (pin "D19") (pinfunction "A5_D19") (pintype "bidirectional"))
    )
    (net (code "70") (name "unconnected-(A3-A6-PadD20)") (class "Default")
      (node (ref "A3") (pin "D20") (pinfunction "A6_D20") (pintype "bidirectional"))
    )
    (net (code "71") (name "unconnected-(A3-A7-PadD21)") (class "Default")
      (node (ref "A3") (pin "D21") (pinfunction "A7_D21") (pintype "bidirectional"))
    )
    (net (code "72") (name "unconnected-(A3-A8-PadD22)") (class "Default")
      (node (ref "A3") (pin "D22") (pinfunction "A8_D22") (pintype "bidirectional"))
    )
    (net (code "73") (name "unconnected-(A3-A9-PadD23)") (class "Default")
      (node (ref "A3") (pin "D23") (pinfunction "A9_D23") (pintype "bidirectional"))
    )
    (net (code "74") (name "unconnected-(J10-Pad8)") (class "Default")
      (node (ref "J10") (pin "8") (pinfunction "8_8") (pintype "passive"))
    )
    (net (code "75") (name "unconnected-(J10-Pad9)") (class "Default")
      (node (ref "J10") (pin "9") (pinfunction "9_9") (pintype "passive"))
    )
    (net (code "76") (name "unconnected-(J14-Pad2)") (class "Default")
      (node (ref "J14") (pin "2") (pinfunction "2_2") (pintype "passive"))
    )
    (net (code "77") (name "unconnected-(J16-Pad8)") (class "Default")
      (node (ref "J16") (pin "8") (pinfunction "8_8") (pintype "passive"))
    )
    (net (code "78") (name "unconnected-(U10-READY-Pad1)") (class "Default")
      (node (ref "U10") (pin "1") (pinfunction "READY_1") (pintype "output"))
    )
    (net (code "79") (name "unconnected-(U10-~{INVALID}-Pad10)") (class "Default")
      (node (ref "U10") (pin "10") (pinfunction "~{INVALID}_10") (pintype "output"))
    )
    (net (code "80") (name "~{ADC1_CS}") (class "Default")
      (node (ref "A3") (pin "D2") (pinfunction "D2_D2") (pintype "bidirectional"))
      (node (ref "U11") (pin "5") (pinfunction "~{CS}_5") (pintype "input"))
    )
    (net (code "81") (name "~{ADC2_CS}") (class "Default")
      (node (ref "A3") (pin "D3") (pinfunction "D3_D3") (pintype "bidirectional"))
      (node (ref "U12") (pin "5") (pinfunction "~{CS}_5") (pintype "input"))
    )
    (net (code "82") (name "~{ADC3_CS}") (class "Default")
      (node (ref "A3") (pin "D10") (pinfunction "(CS)D10_D10") (pintype "bidirectional"))
      (node (ref "U15") (pin "10") (pinfunction "~{CS}/SHDN_10") (pintype "input"))
    )
  )
)
